# eightbyeight-ICN2012.net
KiCad netlist of a schematic drawn in EAGLE
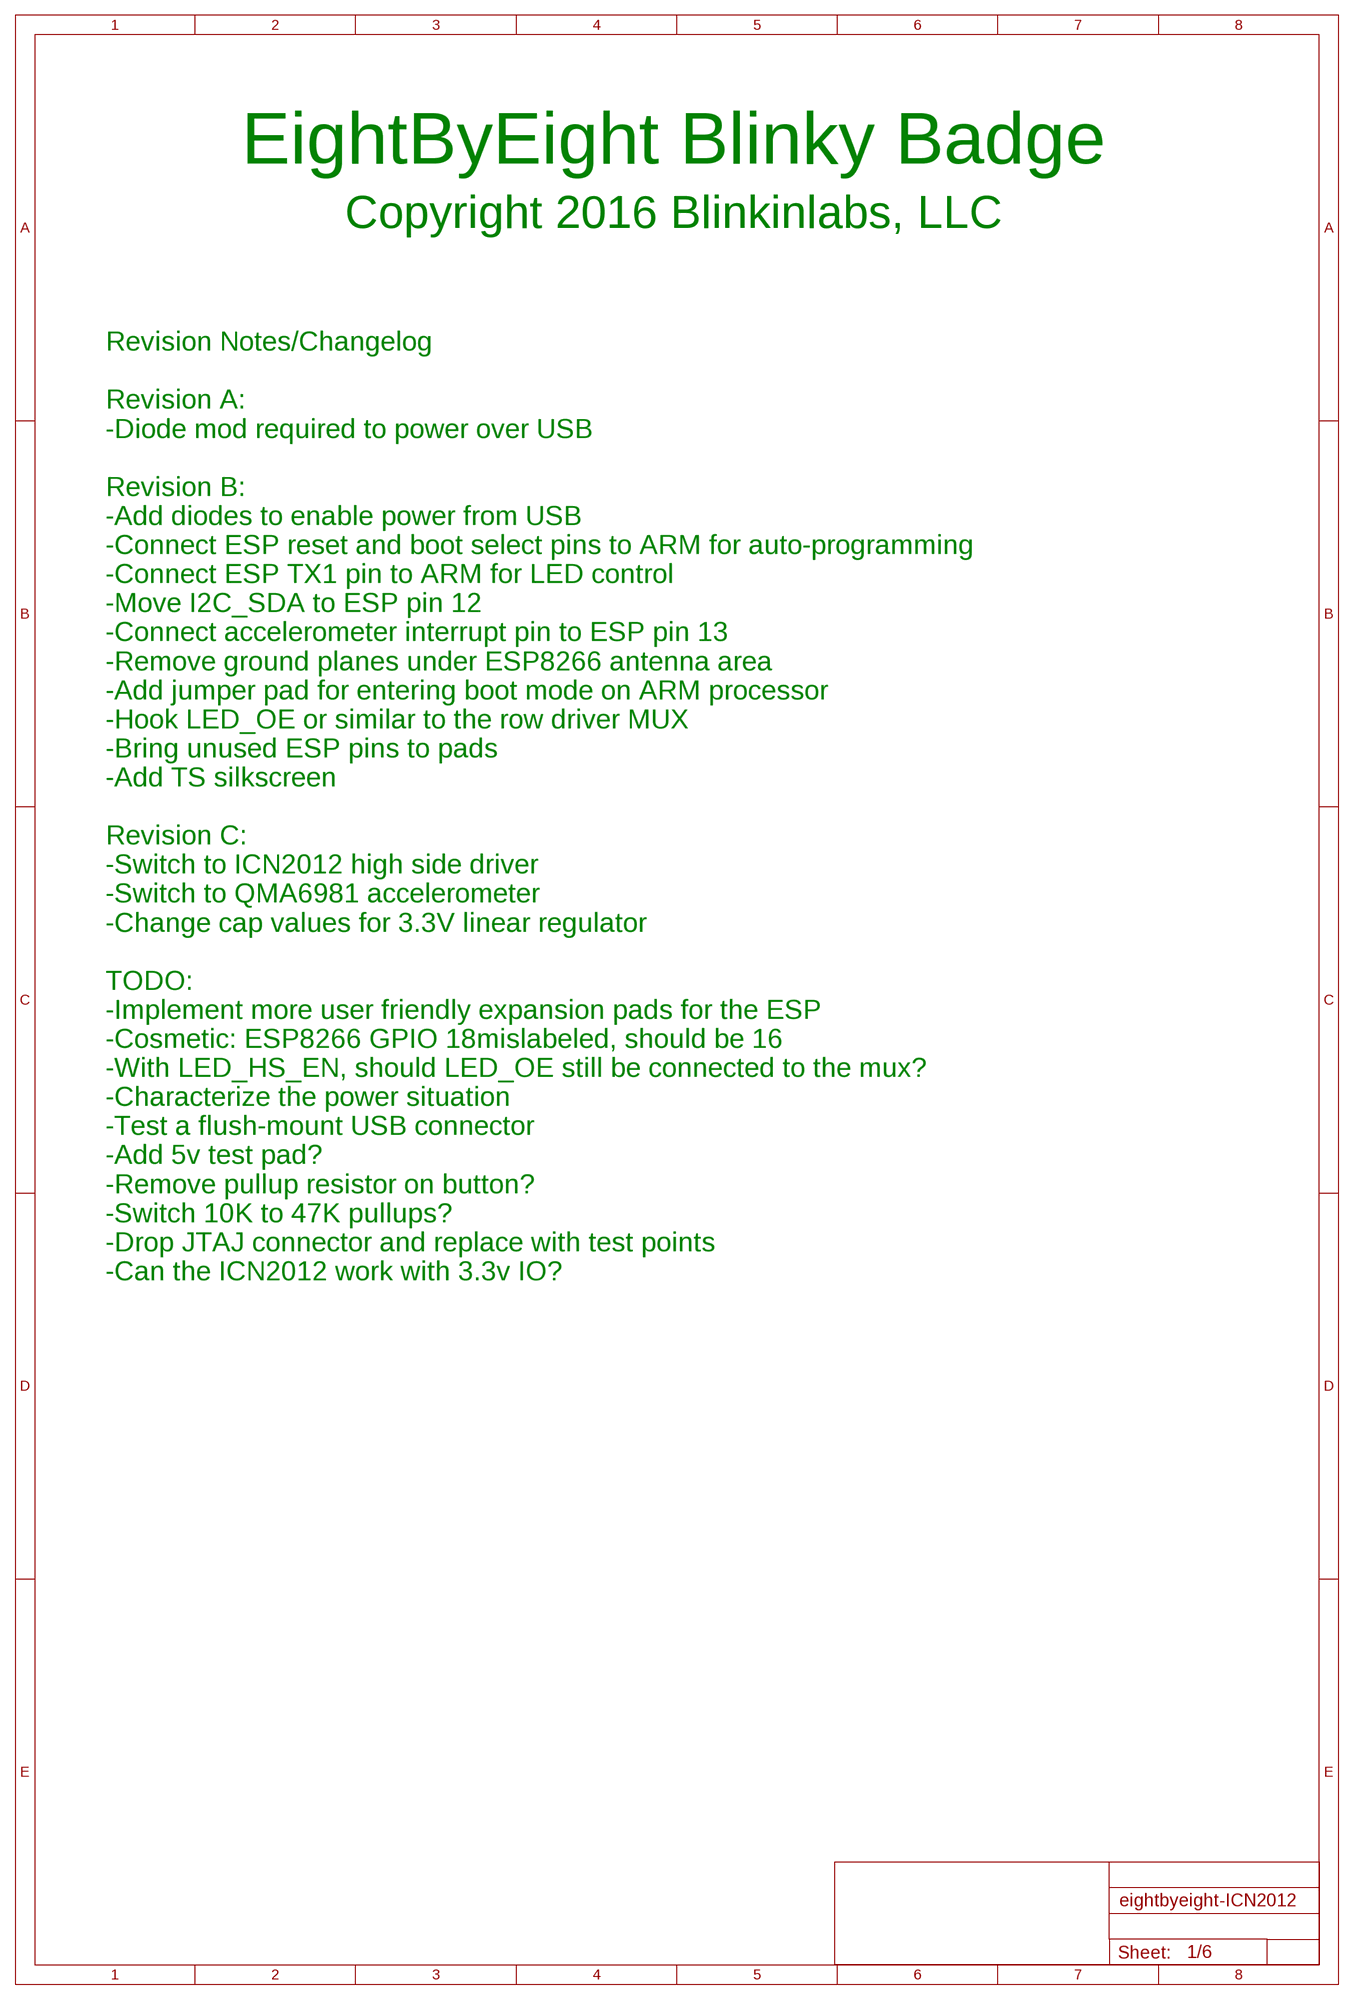
[diagram p0: schematic, sheet 1]
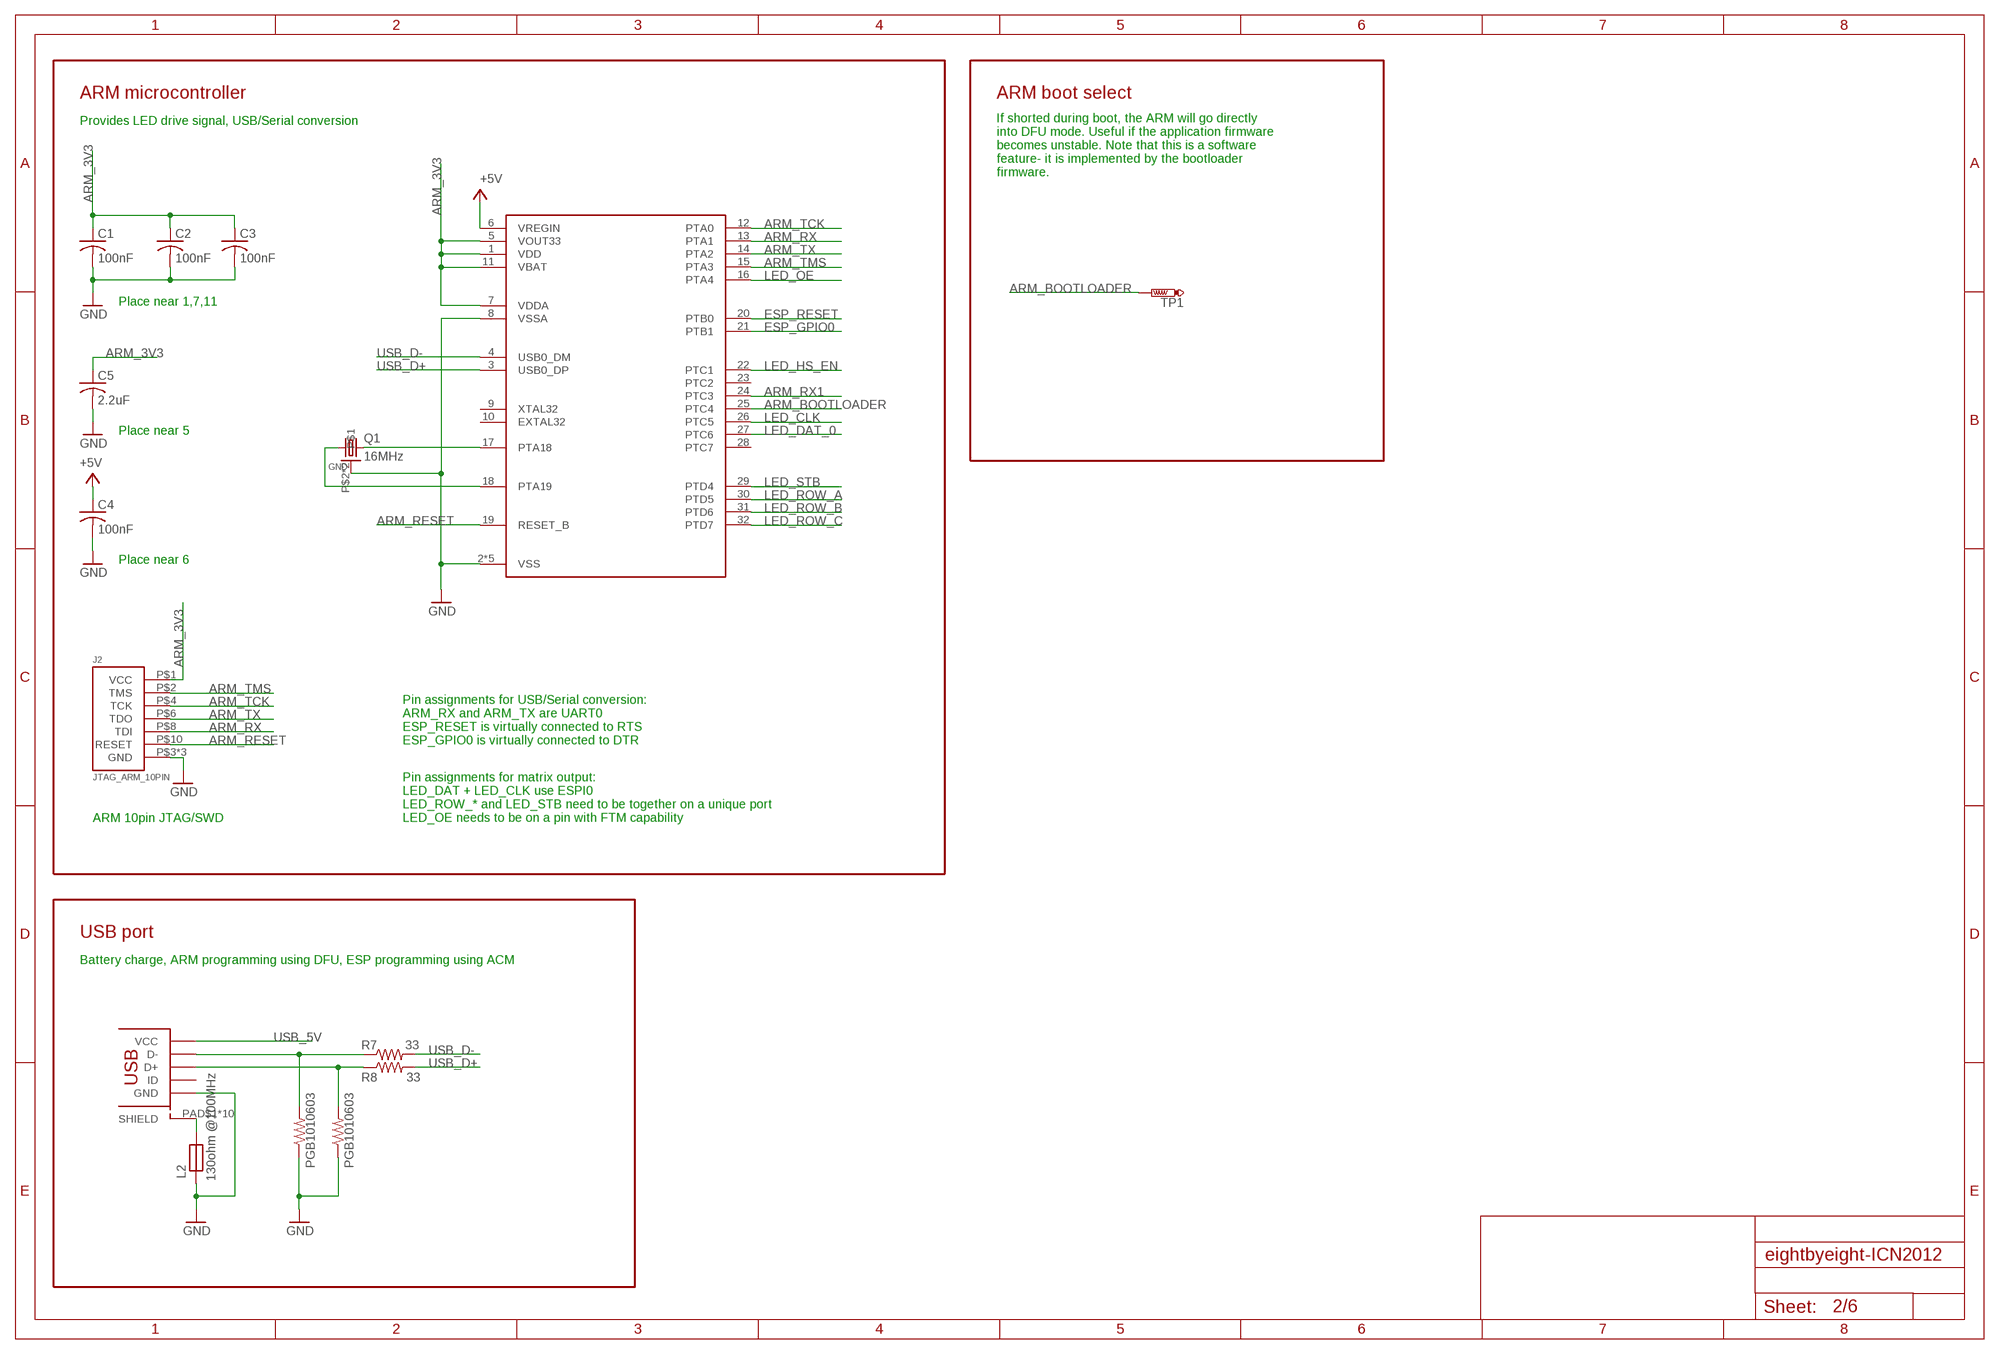
[diagram p1: schematic, sheet 2]
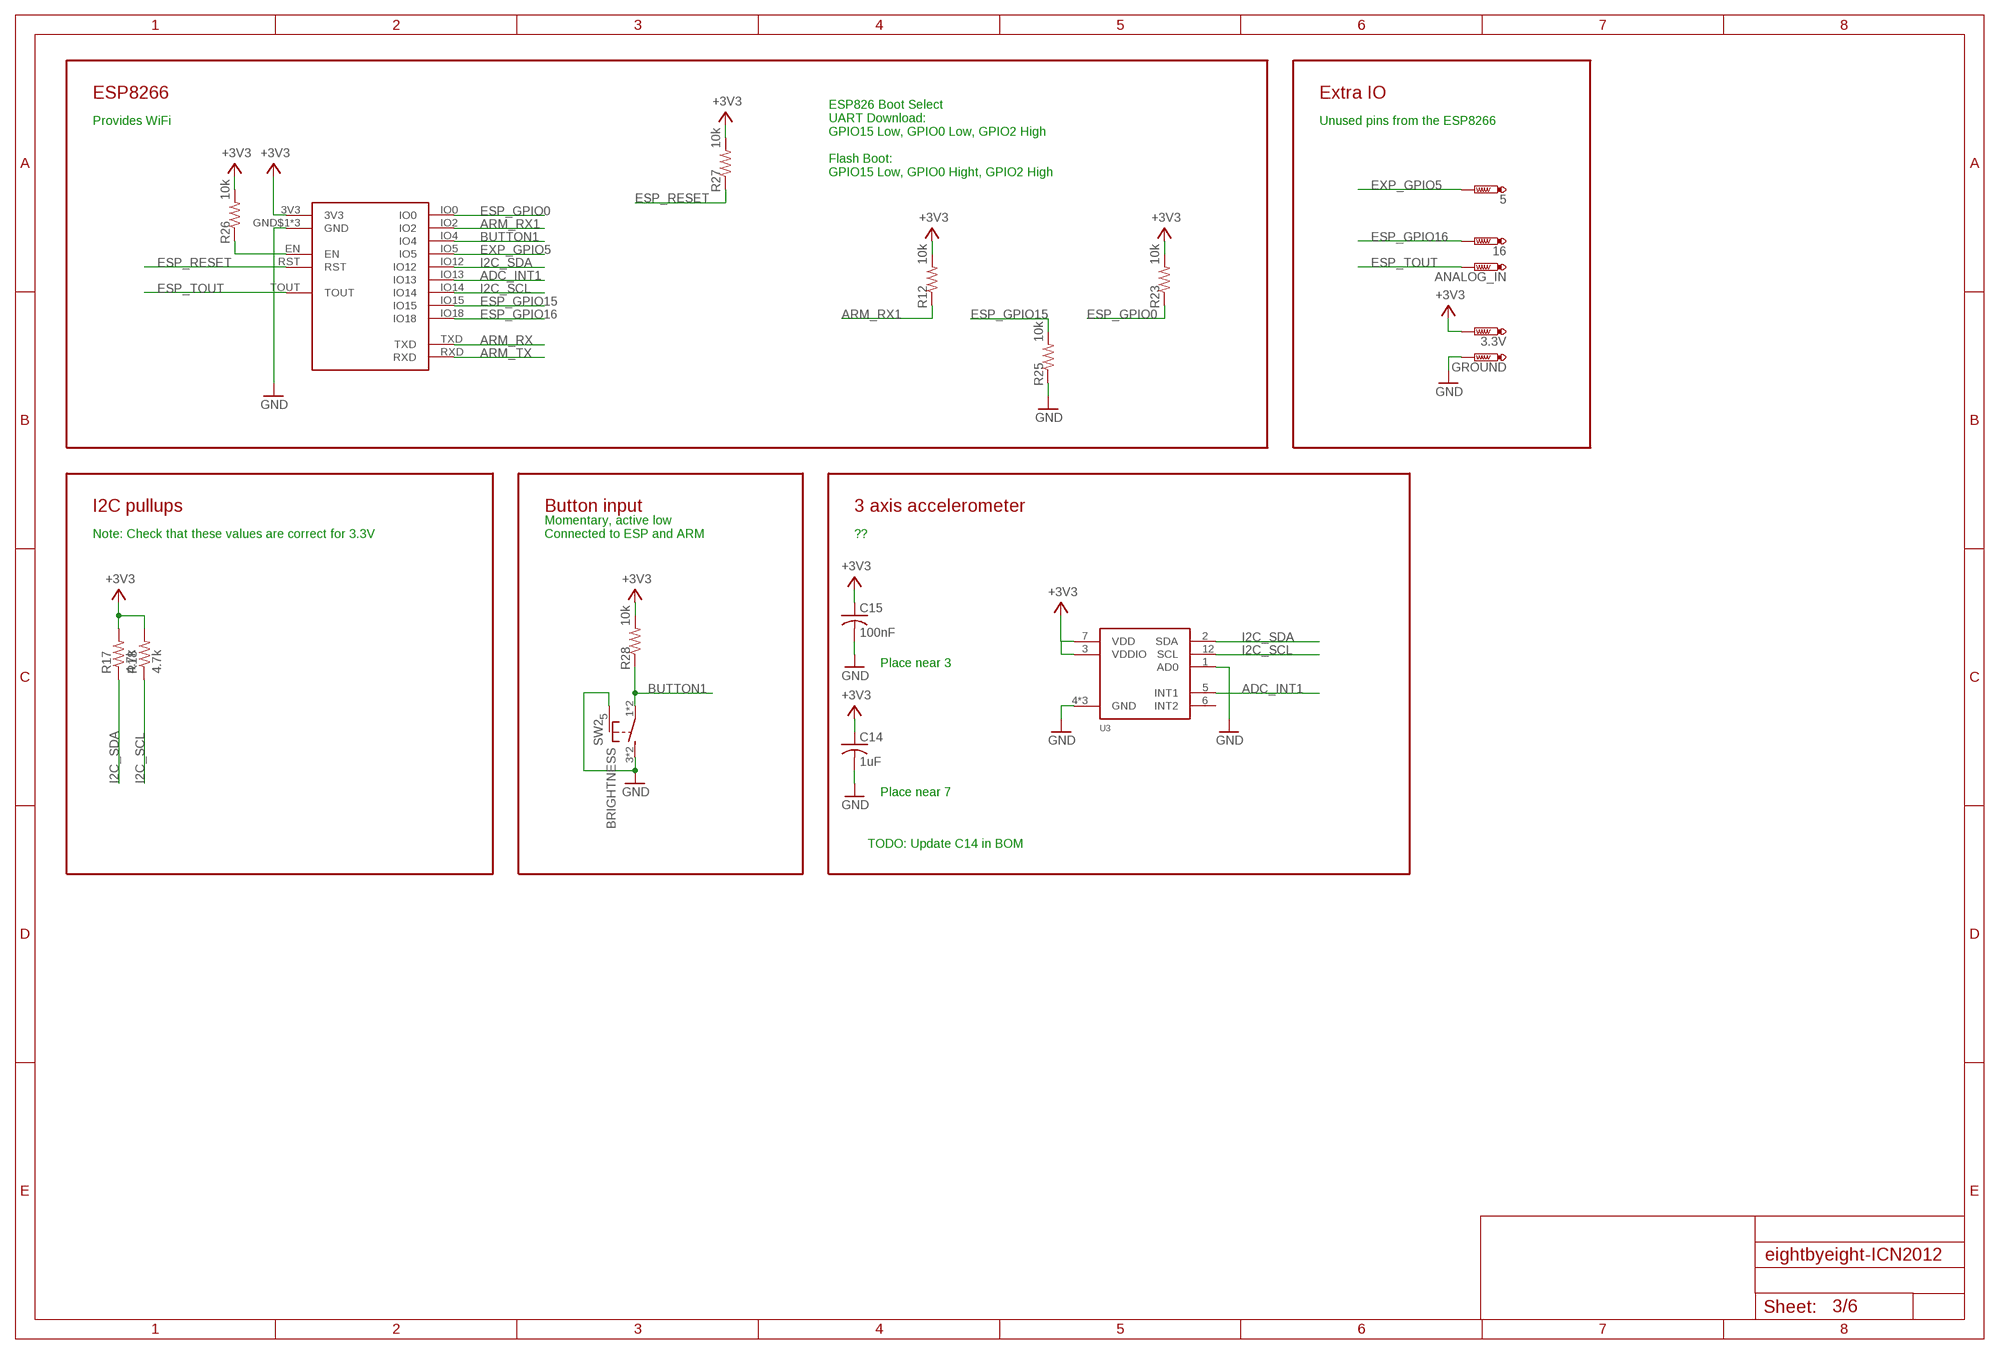
[diagram p2: schematic, sheet 3]
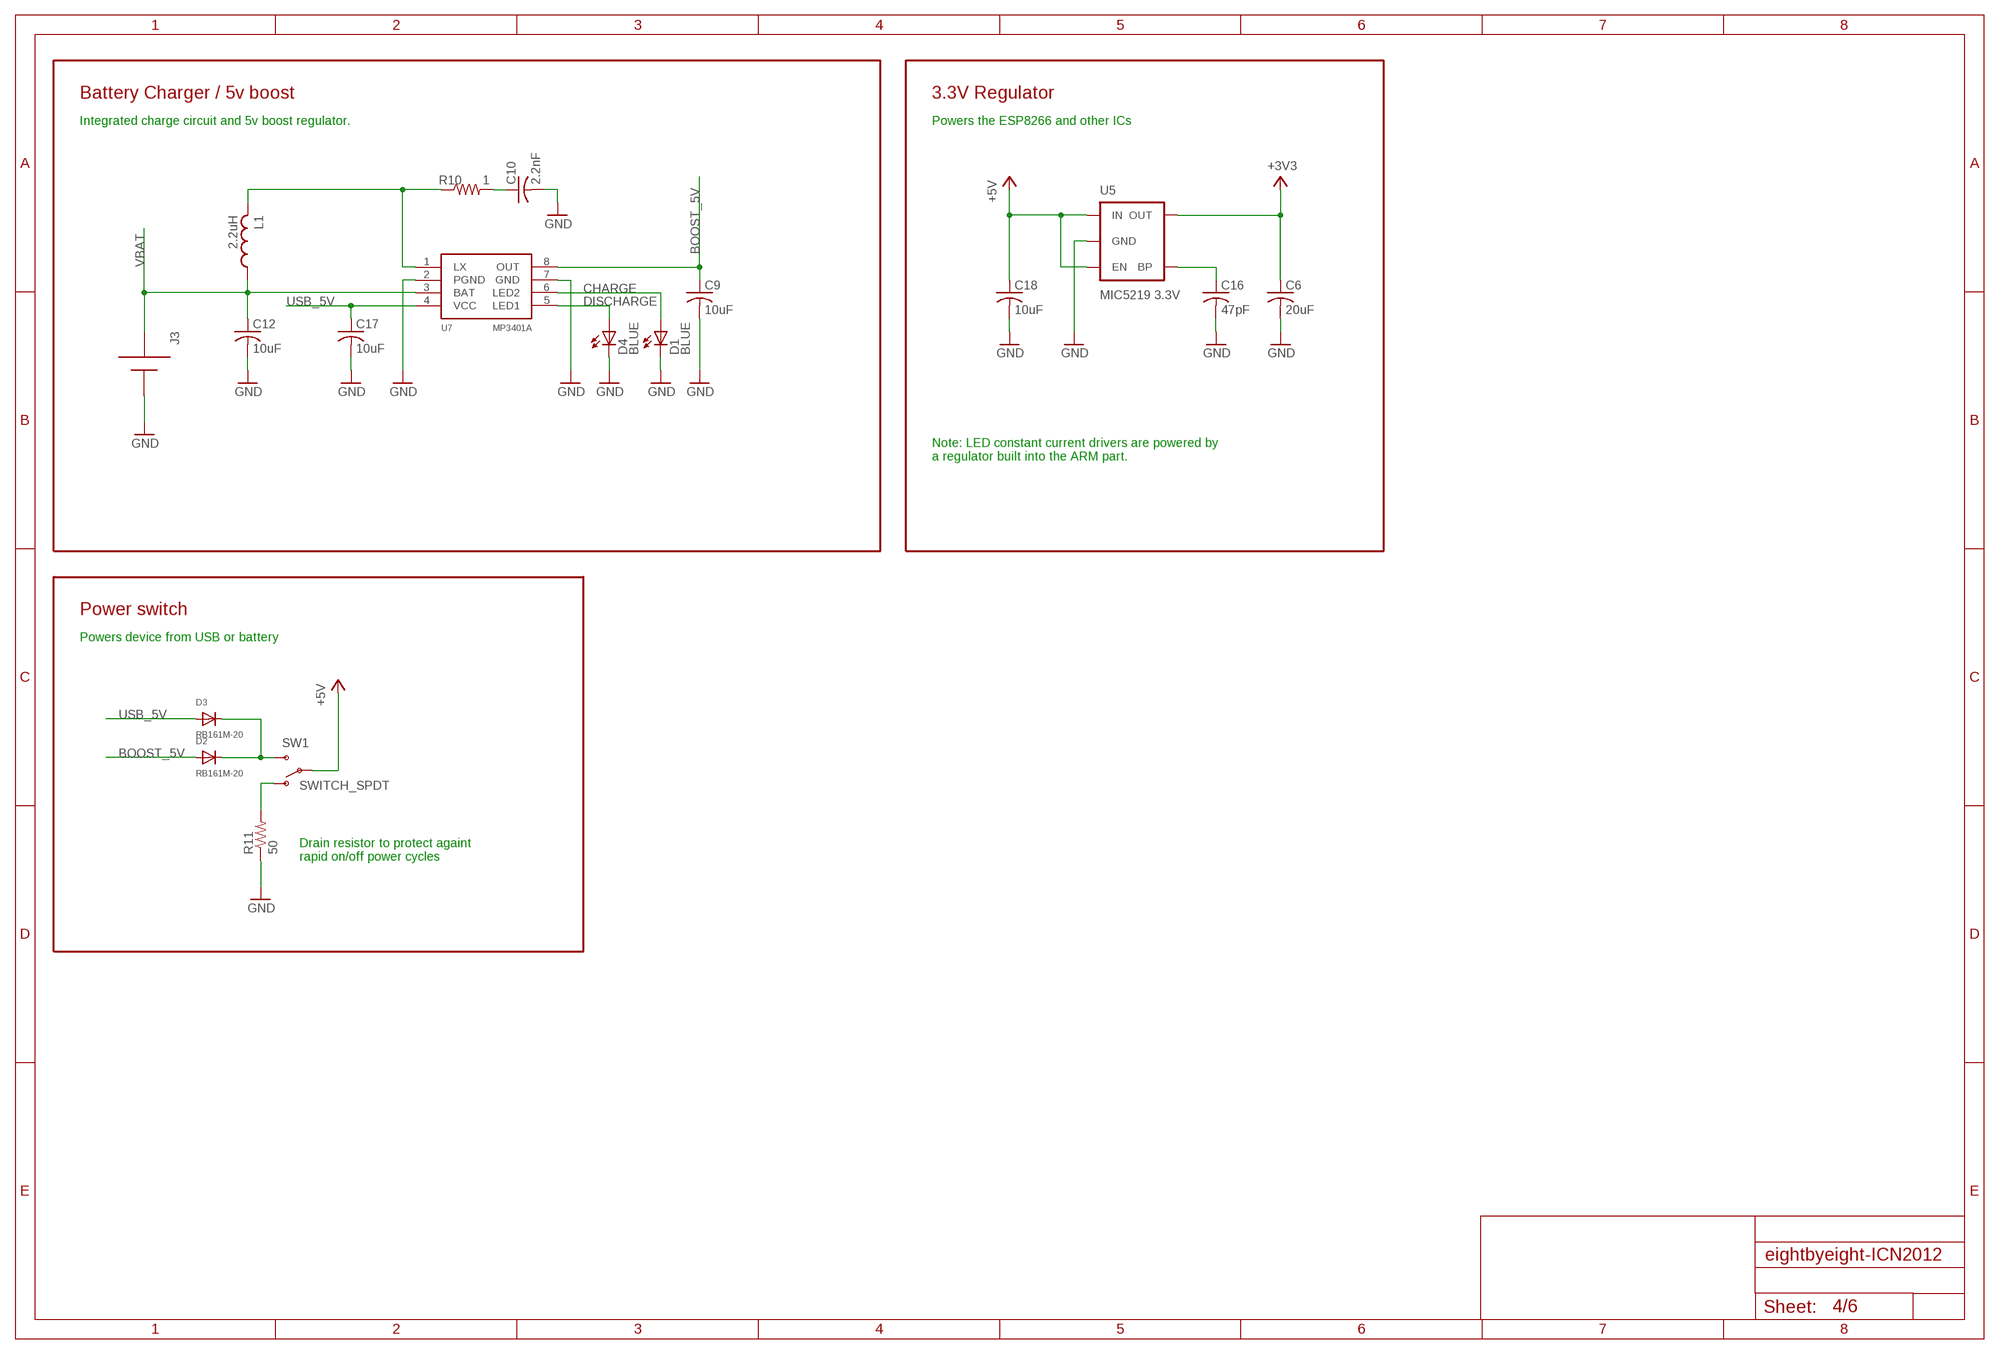
[diagram p3: schematic, sheet 4]
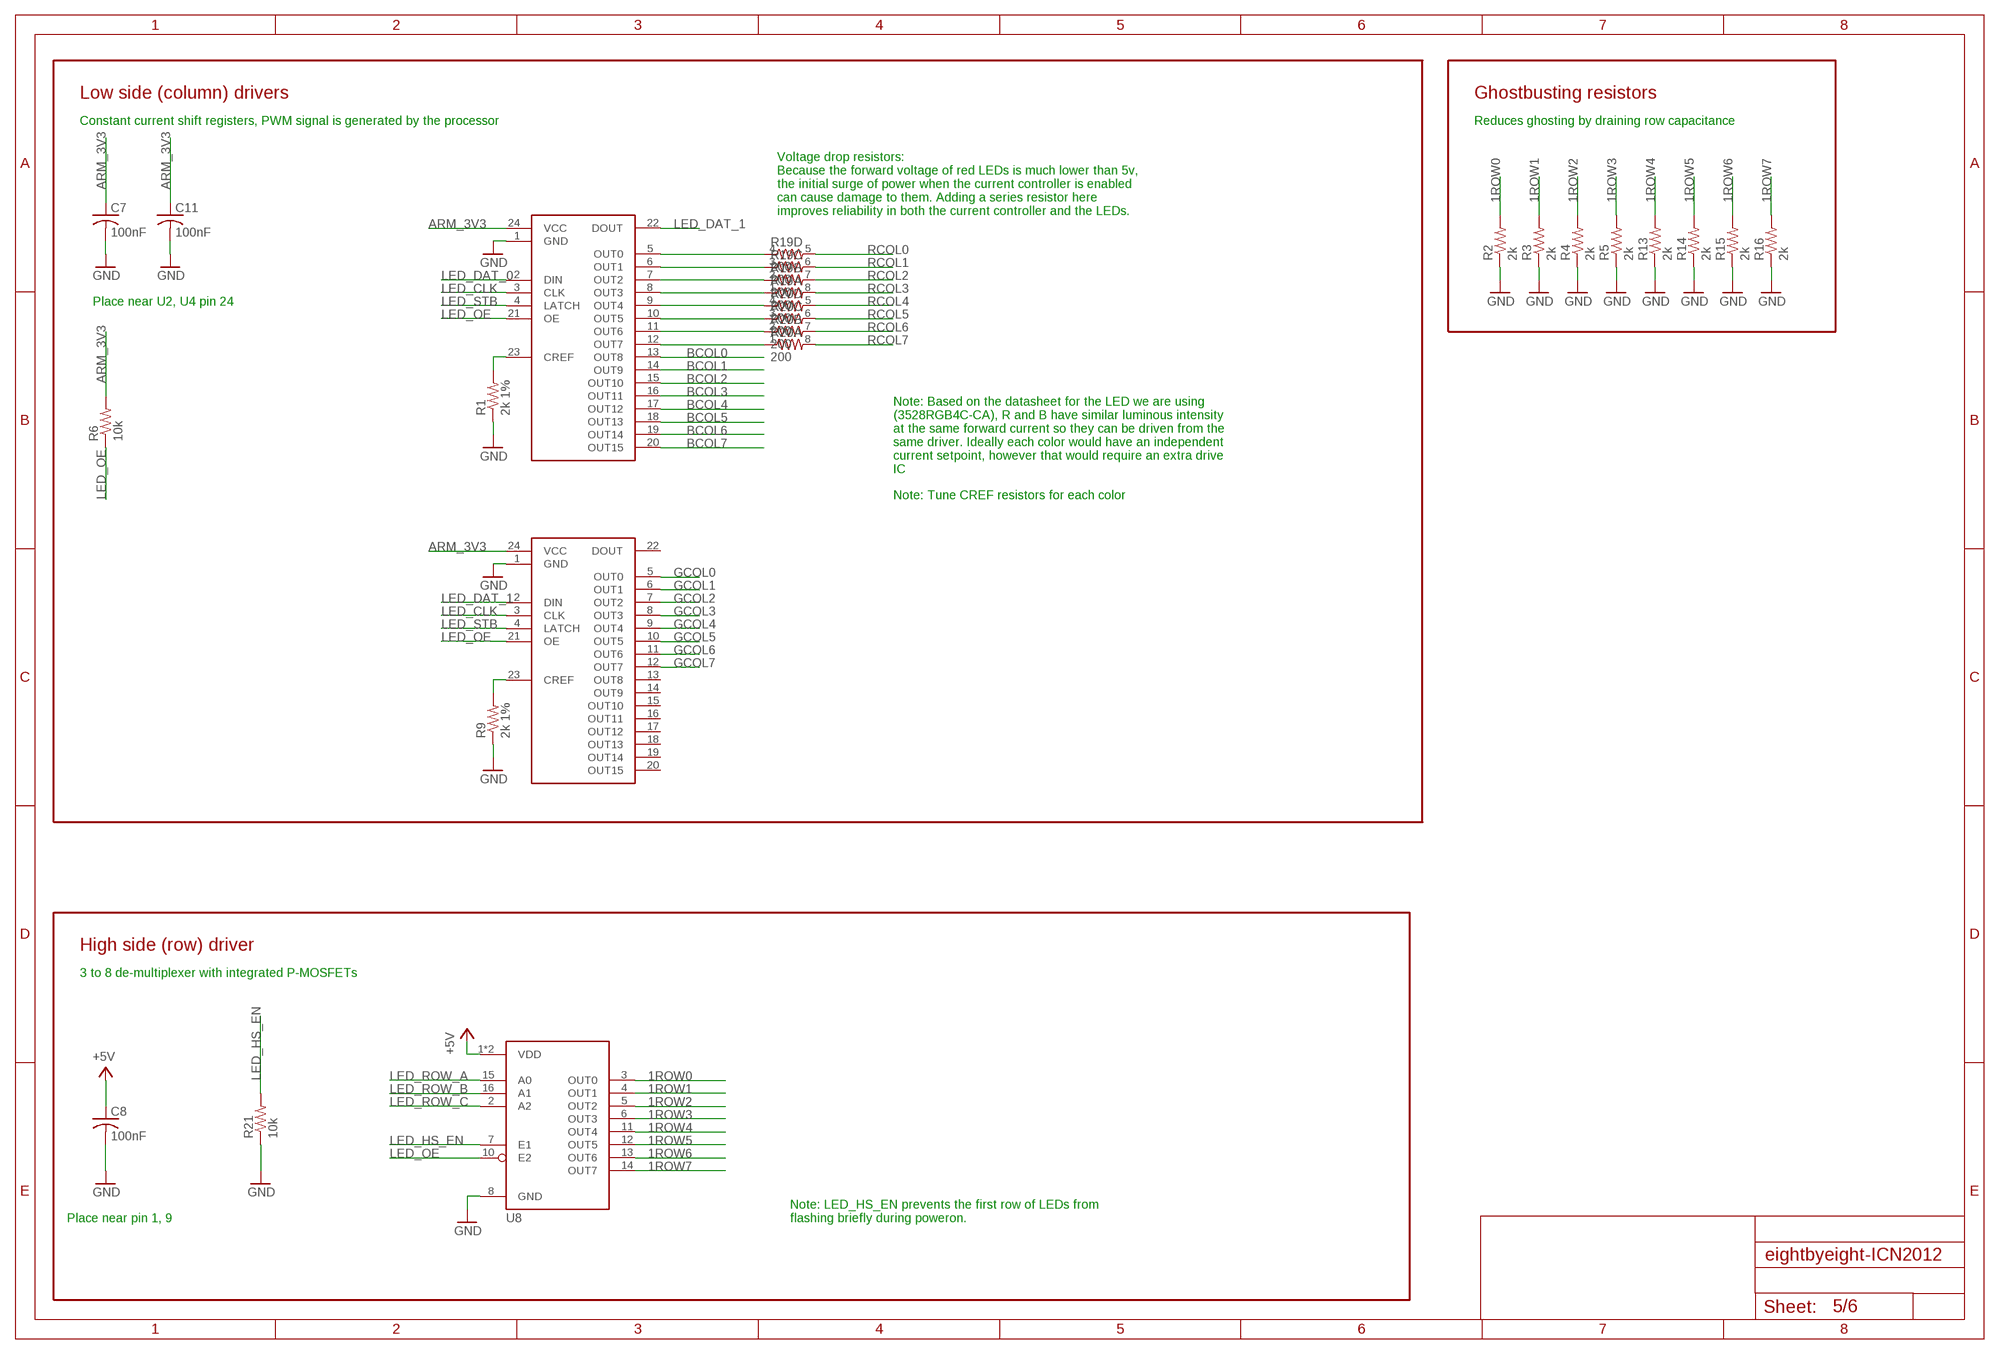
[diagram p4: schematic, sheet 5]
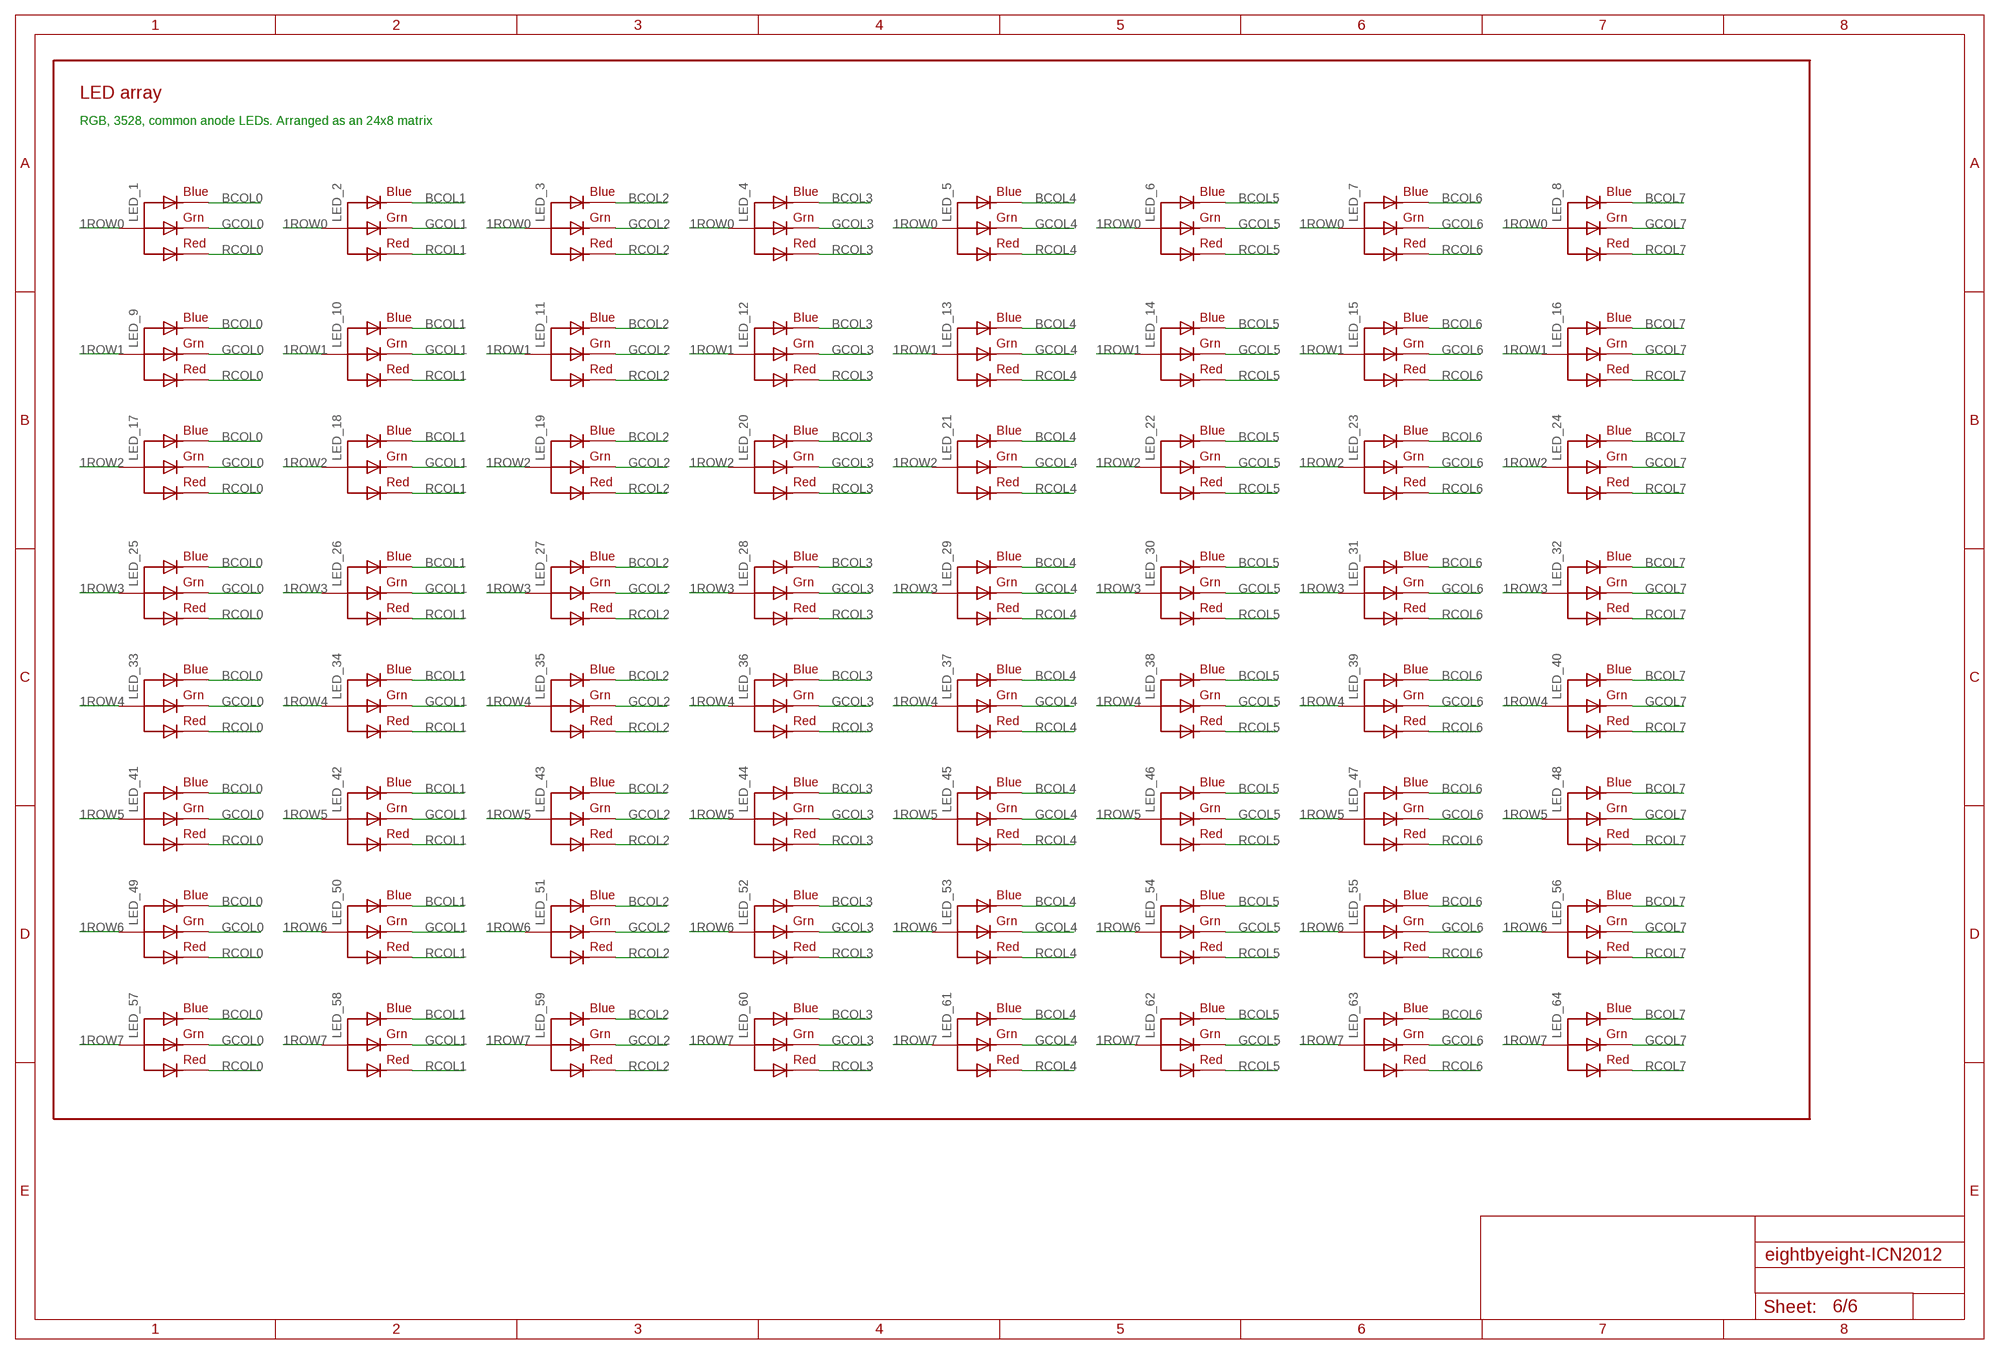
[diagram p5: schematic, sheet 6]

(export (version "E")
  (design (tool "Eeschema 10.0.6"))
  (components
    (comp (ref "LED_1")
      (value "LED_RGB_CA")
      (footprint "eagle-import:LED_3528")
      (libsource (lib "eagle-import") (part "LED_RGB_CA"))
    )
    (comp (ref "LED_2")
      (value "LED_RGB_CA")
      (footprint "eagle-import:LED_3528")
      (libsource (lib "eagle-import") (part "LED_RGB_CA"))
    )
    (comp (ref "LED_3")
      (value "LED_RGB_CA")
      (footprint "eagle-import:LED_3528")
      (libsource (lib "eagle-import") (part "LED_RGB_CA"))
    )
    (comp (ref "LED_4")
      (value "LED_RGB_CA")
      (footprint "eagle-import:LED_3528")
      (libsource (lib "eagle-import") (part "LED_RGB_CA"))
    )
    (comp (ref "LED_5")
      (value "LED_RGB_CA")
      (footprint "eagle-import:LED_3528")
      (libsource (lib "eagle-import") (part "LED_RGB_CA"))
    )
    (comp (ref "LED_6")
      (value "LED_RGB_CA")
      (footprint "eagle-import:LED_3528")
      (libsource (lib "eagle-import") (part "LED_RGB_CA"))
    )
    (comp (ref "LED_7")
      (value "LED_RGB_CA")
      (footprint "eagle-import:LED_3528")
      (libsource (lib "eagle-import") (part "LED_RGB_CA"))
    )
    (comp (ref "LED_8")
      (value "LED_RGB_CA")
      (footprint "eagle-import:LED_3528")
      (libsource (lib "eagle-import") (part "LED_RGB_CA"))
    )
    (comp (ref "LED_9")
      (value "LED_RGB_CA")
      (footprint "eagle-import:LED_3528")
      (libsource (lib "eagle-import") (part "LED_RGB_CA"))
    )
    (comp (ref "LED_10")
      (value "LED_RGB_CA")
      (footprint "eagle-import:LED_3528")
      (libsource (lib "eagle-import") (part "LED_RGB_CA"))
    )
    (comp (ref "LED_11")
      (value "LED_RGB_CA")
      (footprint "eagle-import:LED_3528")
      (libsource (lib "eagle-import") (part "LED_RGB_CA"))
    )
    (comp (ref "LED_12")
      (value "LED_RGB_CA")
      (footprint "eagle-import:LED_3528")
      (libsource (lib "eagle-import") (part "LED_RGB_CA"))
    )
    (comp (ref "LED_13")
      (value "LED_RGB_CA")
      (footprint "eagle-import:LED_3528")
      (libsource (lib "eagle-import") (part "LED_RGB_CA"))
    )
    (comp (ref "LED_14")
      (value "LED_RGB_CA")
      (footprint "eagle-import:LED_3528")
      (libsource (lib "eagle-import") (part "LED_RGB_CA"))
    )
    (comp (ref "LED_15")
      (value "LED_RGB_CA")
      (footprint "eagle-import:LED_3528")
      (libsource (lib "eagle-import") (part "LED_RGB_CA"))
    )
    (comp (ref "LED_16")
      (value "LED_RGB_CA")
      (footprint "eagle-import:LED_3528")
      (libsource (lib "eagle-import") (part "LED_RGB_CA"))
    )
    (comp (ref "LED_17")
      (value "LED_RGB_CA")
      (footprint "eagle-import:LED_3528")
      (libsource (lib "eagle-import") (part "LED_RGB_CA"))
    )
    (comp (ref "LED_18")
      (value "LED_RGB_CA")
      (footprint "eagle-import:LED_3528")
      (libsource (lib "eagle-import") (part "LED_RGB_CA"))
    )
    (comp (ref "LED_19")
      (value "LED_RGB_CA")
      (footprint "eagle-import:LED_3528")
      (libsource (lib "eagle-import") (part "LED_RGB_CA"))
    )
    (comp (ref "LED_20")
      (value "LED_RGB_CA")
      (footprint "eagle-import:LED_3528")
      (libsource (lib "eagle-import") (part "LED_RGB_CA"))
    )
    (comp (ref "LED_21")
      (value "LED_RGB_CA")
      (footprint "eagle-import:LED_3528")
      (libsource (lib "eagle-import") (part "LED_RGB_CA"))
    )
    (comp (ref "LED_22")
      (value "LED_RGB_CA")
      (footprint "eagle-import:LED_3528")
      (libsource (lib "eagle-import") (part "LED_RGB_CA"))
    )
    (comp (ref "LED_23")
      (value "LED_RGB_CA")
      (footprint "eagle-import:LED_3528")
      (libsource (lib "eagle-import") (part "LED_RGB_CA"))
    )
    (comp (ref "LED_24")
      (value "LED_RGB_CA")
      (footprint "eagle-import:LED_3528")
      (libsource (lib "eagle-import") (part "LED_RGB_CA"))
    )
    (comp (ref "LED_25")
      (value "LED_RGB_CA")
      (footprint "eagle-import:LED_3528")
      (libsource (lib "eagle-import") (part "LED_RGB_CA"))
    )
    (comp (ref "LED_26")
      (value "LED_RGB_CA")
      (footprint "eagle-import:LED_3528")
      (libsource (lib "eagle-import") (part "LED_RGB_CA"))
    )
    (comp (ref "LED_27")
      (value "LED_RGB_CA")
      (footprint "eagle-import:LED_3528")
      (libsource (lib "eagle-import") (part "LED_RGB_CA"))
    )
    (comp (ref "LED_28")
      (value "LED_RGB_CA")
      (footprint "eagle-import:LED_3528")
      (libsource (lib "eagle-import") (part "LED_RGB_CA"))
    )
    (comp (ref "LED_29")
      (value "LED_RGB_CA")
      (footprint "eagle-import:LED_3528")
      (libsource (lib "eagle-import") (part "LED_RGB_CA"))
    )
    (comp (ref "LED_30")
      (value "LED_RGB_CA")
      (footprint "eagle-import:LED_3528")
      (libsource (lib "eagle-import") (part "LED_RGB_CA"))
    )
    (comp (ref "LED_31")
      (value "LED_RGB_CA")
      (footprint "eagle-import:LED_3528")
      (libsource (lib "eagle-import") (part "LED_RGB_CA"))
    )
    (comp (ref "LED_32")
      (value "LED_RGB_CA")
      (footprint "eagle-import:LED_3528")
      (libsource (lib "eagle-import") (part "LED_RGB_CA"))
    )
    (comp (ref "LED_33")
      (value "LED_RGB_CA")
      (footprint "eagle-import:LED_3528")
      (libsource (lib "eagle-import") (part "LED_RGB_CA"))
    )
    (comp (ref "LED_34")
      (value "LED_RGB_CA")
      (footprint "eagle-import:LED_3528")
      (libsource (lib "eagle-import") (part "LED_RGB_CA"))
    )
    (comp (ref "LED_35")
      (value "LED_RGB_CA")
      (footprint "eagle-import:LED_3528")
      (libsource (lib "eagle-import") (part "LED_RGB_CA"))
    )
    (comp (ref "LED_36")
      (value "LED_RGB_CA")
      (footprint "eagle-import:LED_3528")
      (libsource (lib "eagle-import") (part "LED_RGB_CA"))
    )
    (comp (ref "LED_37")
      (value "LED_RGB_CA")
      (footprint "eagle-import:LED_3528")
      (libsource (lib "eagle-import") (part "LED_RGB_CA"))
    )
    (comp (ref "LED_38")
      (value "LED_RGB_CA")
      (footprint "eagle-import:LED_3528")
      (libsource (lib "eagle-import") (part "LED_RGB_CA"))
    )
    (comp (ref "LED_39")
      (value "LED_RGB_CA")
      (footprint "eagle-import:LED_3528")
      (libsource (lib "eagle-import") (part "LED_RGB_CA"))
    )
    (comp (ref "LED_40")
      (value "LED_RGB_CA")
      (footprint "eagle-import:LED_3528")
      (libsource (lib "eagle-import") (part "LED_RGB_CA"))
    )
    (comp (ref "LED_41")
      (value "LED_RGB_CA")
      (footprint "eagle-import:LED_3528")
      (libsource (lib "eagle-import") (part "LED_RGB_CA"))
    )
    (comp (ref "LED_42")
      (value "LED_RGB_CA")
      (footprint "eagle-import:LED_3528")
      (libsource (lib "eagle-import") (part "LED_RGB_CA"))
    )
    (comp (ref "LED_43")
      (value "LED_RGB_CA")
      (footprint "eagle-import:LED_3528")
      (libsource (lib "eagle-import") (part "LED_RGB_CA"))
    )
    (comp (ref "LED_44")
      (value "LED_RGB_CA")
      (footprint "eagle-import:LED_3528")
      (libsource (lib "eagle-import") (part "LED_RGB_CA"))
    )
    (comp (ref "LED_45")
      (value "LED_RGB_CA")
      (footprint "eagle-import:LED_3528")
      (libsource (lib "eagle-import") (part "LED_RGB_CA"))
    )
    (comp (ref "LED_46")
      (value "LED_RGB_CA")
      (footprint "eagle-import:LED_3528")
      (libsource (lib "eagle-import") (part "LED_RGB_CA"))
    )
    (comp (ref "LED_47")
      (value "LED_RGB_CA")
      (footprint "eagle-import:LED_3528")
      (libsource (lib "eagle-import") (part "LED_RGB_CA"))
    )
    (comp (ref "LED_48")
      (value "LED_RGB_CA")
      (footprint "eagle-import:LED_3528")
      (libsource (lib "eagle-import") (part "LED_RGB_CA"))
    )
    (comp (ref "LED_49")
      (value "LED_RGB_CA")
      (footprint "eagle-import:LED_3528")
      (libsource (lib "eagle-import") (part "LED_RGB_CA"))
    )
    (comp (ref "LED_50")
      (value "LED_RGB_CA")
      (footprint "eagle-import:LED_3528")
      (libsource (lib "eagle-import") (part "LED_RGB_CA"))
    )
    (comp (ref "LED_51")
      (value "LED_RGB_CA")
      (footprint "eagle-import:LED_3528")
      (libsource (lib "eagle-import") (part "LED_RGB_CA"))
    )
    (comp (ref "LED_52")
      (value "LED_RGB_CA")
      (footprint "eagle-import:LED_3528")
      (libsource (lib "eagle-import") (part "LED_RGB_CA"))
    )
    (comp (ref "LED_53")
      (value "LED_RGB_CA")
      (footprint "eagle-import:LED_3528")
      (libsource (lib "eagle-import") (part "LED_RGB_CA"))
    )
    (comp (ref "LED_54")
      (value "LED_RGB_CA")
      (footprint "eagle-import:LED_3528")
      (libsource (lib "eagle-import") (part "LED_RGB_CA"))
    )
    (comp (ref "LED_55")
      (value "LED_RGB_CA")
      (footprint "eagle-import:LED_3528")
      (libsource (lib "eagle-import") (part "LED_RGB_CA"))
    )
    (comp (ref "LED_56")
      (value "LED_RGB_CA")
      (footprint "eagle-import:LED_3528")
      (libsource (lib "eagle-import") (part "LED_RGB_CA"))
    )
    (comp (ref "LED_57")
      (value "LED_RGB_CA")
      (footprint "eagle-import:LED_3528")
      (libsource (lib "eagle-import") (part "LED_RGB_CA"))
    )
    (comp (ref "LED_58")
      (value "LED_RGB_CA")
      (footprint "eagle-import:LED_3528")
      (libsource (lib "eagle-import") (part "LED_RGB_CA"))
    )
    (comp (ref "LED_59")
      (value "LED_RGB_CA")
      (footprint "eagle-import:LED_3528")
      (libsource (lib "eagle-import") (part "LED_RGB_CA"))
    )
    (comp (ref "LED_60")
      (value "LED_RGB_CA")
      (footprint "eagle-import:LED_3528")
      (libsource (lib "eagle-import") (part "LED_RGB_CA"))
    )
    (comp (ref "LED_61")
      (value "LED_RGB_CA")
      (footprint "eagle-import:LED_3528")
      (libsource (lib "eagle-import") (part "LED_RGB_CA"))
    )
    (comp (ref "LED_62")
      (value "LED_RGB_CA")
      (footprint "eagle-import:LED_3528")
      (libsource (lib "eagle-import") (part "LED_RGB_CA"))
    )
    (comp (ref "LED_63")
      (value "LED_RGB_CA")
      (footprint "eagle-import:LED_3528")
      (libsource (lib "eagle-import") (part "LED_RGB_CA"))
    )
    (comp (ref "LED_64")
      (value "LED_RGB_CA")
      (footprint "eagle-import:LED_3528")
      (libsource (lib "eagle-import") (part "LED_RGB_CA"))
    )
    (comp (ref "C6")
      (value "20uF")
      (footprint "eagle-import:C0805")
      (libsource (lib "eagle-import") (part "C-USC0805"))
    )
    (comp (ref "C9")
      (value "10uF")
      (footprint "eagle-import:C0805")
      (libsource (lib "eagle-import") (part "C-USC0805"))
    )
    (comp (ref "C10")
      (value "2.2nF")
      (footprint "eagle-import:C0603")
      (libsource (lib "eagle-import") (part "C-USC0603"))
    )
    (comp (ref "C12")
      (value "10uF")
      (footprint "eagle-import:C0805")
      (libsource (lib "eagle-import") (part "C-USC0805"))
    )
    (comp (ref "C16")
      (value "47pF")
      (footprint "eagle-import:C0402")
      (libsource (lib "eagle-import") (part "C-USC0402"))
    )
    (comp (ref "C17")
      (value "10uF")
      (footprint "eagle-import:C0805")
      (libsource (lib "eagle-import") (part "C-USC0805"))
    )
    (comp (ref "C18")
      (value "10uF")
      (footprint "eagle-import:C0805")
      (libsource (lib "eagle-import") (part "C-USC0805"))
    )
    (comp (ref "D1")
      (value "BLUE")
      (footprint "eagle-import:CHIP-LED0603")
      (libsource (lib "eagle-import") (part "LEDCHIP-LED0603"))
    )
    (comp (ref "D2")
      (value "RB161M-20")
      (footprint "eagle-import:SOD-123")
      (libsource (lib "eagle-import") (part "DIODESOD-123"))
    )
    (comp (ref "D3")
      (value "RB161M-20")
      (footprint "eagle-import:SOD-123")
      (libsource (lib "eagle-import") (part "DIODESOD-123"))
    )
    (comp (ref "D4")
      (value "BLUE")
      (footprint "eagle-import:CHIP-LED0603")
      (libsource (lib "eagle-import") (part "LEDCHIP-LED0603"))
    )
    (comp (ref "J3")
      (value "BATTERY")
      (footprint "eagle-import:BATTERY_AA_SMD")
      (libsource (lib "eagle-import") (part "BATTERY"))
    )
    (comp (ref "L1")
      (value "2.2uH")
      (footprint "eagle-import:INDUCTOR_CD43")
      (libsource (lib "eagle-import") (part "LCD43"))
    )
    (comp (ref "R10")
      (value "1")
      (footprint "eagle-import:R0603")
      (libsource (lib "eagle-import") (part "R-US_R0603"))
    )
    (comp (ref "R11")
      (value "50")
      (footprint "eagle-import:R0805")
      (libsource (lib "eagle-import") (part "R-US_R0805"))
    )
    (comp (ref "SW1")
      (value "SWITCH_SPDT")
      (footprint "eagle-import:SWITCH_6P-2POS")
      (libsource (lib "eagle-import") (part "SWITCH_SPDT"))
    )
    (comp (ref "U5")
      (value "MIC5219 3.3V")
      (footprint "eagle-import:SOT23-5")
      (libsource (lib "eagle-import") (part "V_REG_MIC52193.3V"))
    )
    (comp (ref "U7")
      (value "MP3401A")
      (footprint "eagle-import:SO08-150")
      (libsource (lib "eagle-import") (part "MP3401A"))
    )
    (comp (ref "C7")
      (value "100nF")
      (footprint "eagle-import:C0402")
      (libsource (lib "eagle-import") (part "C-USC0402"))
    )
    (comp (ref "C8")
      (value "100nF")
      (footprint "eagle-import:C0402")
      (libsource (lib "eagle-import") (part "C-USC0402"))
    )
    (comp (ref "C11")
      (value "100nF")
      (footprint "eagle-import:C0402")
      (libsource (lib "eagle-import") (part "C-USC0402"))
    )
    (comp (ref "R1")
      (value "2k 1%")
      (footprint "eagle-import:R0402")
      (libsource (lib "eagle-import") (part "R-US_R0402"))
    )
    (comp (ref "R2")
      (value "2k")
      (footprint "eagle-import:R0402")
      (libsource (lib "eagle-import") (part "R-US_R0402"))
    )
    (comp (ref "R3")
      (value "2k")
      (footprint "eagle-import:R0402")
      (libsource (lib "eagle-import") (part "R-US_R0402"))
    )
    (comp (ref "R4")
      (value "2k")
      (footprint "eagle-import:R0402")
      (libsource (lib "eagle-import") (part "R-US_R0402"))
    )
    (comp (ref "R5")
      (value "2k")
      (footprint "eagle-import:R0402")
      (libsource (lib "eagle-import") (part "R-US_R0402"))
    )
    (comp (ref "R6")
      (value "10k")
      (footprint "eagle-import:R0402")
      (libsource (lib "eagle-import") (part "R-US_R0402"))
    )
    (comp (ref "R9")
      (value "2k 1%")
      (footprint "eagle-import:R0402")
      (libsource (lib "eagle-import") (part "R-US_R0402"))
    )
    (comp (ref "R13")
      (value "2k")
      (footprint "eagle-import:R0402")
      (libsource (lib "eagle-import") (part "R-US_R0402"))
    )
    (comp (ref "R14")
      (value "2k")
      (footprint "eagle-import:R0402")
      (libsource (lib "eagle-import") (part "R-US_R0402"))
    )
    (comp (ref "R15")
      (value "2k")
      (footprint "eagle-import:R0402")
      (libsource (lib "eagle-import") (part "R-US_R0402"))
    )
    (comp (ref "R16")
      (value "2k")
      (footprint "eagle-import:R0402")
      (libsource (lib "eagle-import") (part "R-US_R0402"))
    )
    (comp (ref "R19")
      (value "200")
      (footprint "eagle-import:0603-ARV")
      (libsource (lib "eagle-import") (part "RESISTOR-ARRAY0603-ARV"))
    )
    (comp (ref "R20")
      (value "200")
      (footprint "eagle-import:0603-ARV")
      (libsource (lib "eagle-import") (part "RESISTOR-ARRAY0603-ARV"))
    )
    (comp (ref "R21")
      (value "10k")
      (footprint "eagle-import:R0402")
      (libsource (lib "eagle-import") (part "R-US_R0402"))
    )
    (comp (ref "U2")
      (value "ICN2027")
      (footprint "eagle-import:SSOP24-150")
      (libsource (lib "eagle-import") (part "ICN2026"))
    )
    (comp (ref "U4")
      (value "ICN2027")
      (footprint "eagle-import:SSOP24-150")
      (libsource (lib "eagle-import") (part "ICN2026"))
    )
    (comp (ref "U8")
      (value "ICN2012")
      (footprint "eagle-import:SO16")
      (libsource (lib "eagle-import") (part "ICN2012"))
    )
    (comp (ref "C1")
      (value "100nF")
      (footprint "eagle-import:C0402")
      (libsource (lib "eagle-import") (part "C-USC0402"))
    )
    (comp (ref "C2")
      (value "100nF")
      (footprint "eagle-import:C0402")
      (libsource (lib "eagle-import") (part "C-USC0402"))
    )
    (comp (ref "C3")
      (value "100nF")
      (footprint "eagle-import:C0402")
      (libsource (lib "eagle-import") (part "C-USC0402"))
    )
    (comp (ref "C4")
      (value "100nF")
      (footprint "eagle-import:C0402")
      (libsource (lib "eagle-import") (part "C-USC0402"))
    )
    (comp (ref "C5")
      (value "2.2uF")
      (footprint "eagle-import:C0402")
      (libsource (lib "eagle-import") (part "C-USC0402"))
    )
    (comp (ref "J1")
      (value "USB_MICROSMT+THRUHULE")
      (footprint "eagle-import:USB_MICRO_THRUHOLE")
      (libsource (lib "eagle-import") (part "USB_MICROSMT+THRUHULE"))
    )
    (comp (ref "J2")
      (value "JTAG_ARM_10PIN")
      (footprint "eagle-import:2X05-1.27MM-SMD")
      (libsource (lib "eagle-import") (part "JTAG_ARM_10PIN"))
    )
    (comp (ref "L2")
      (value "130ohm @100MHz")
      (footprint "eagle-import:0805")
      (libsource (lib "eagle-import") (part "FB0805/NO-OUTLINE"))
    )
    (comp (ref "Q1")
      (value "16MHz")
      (footprint "eagle-import:CRSYTAL_2520")
      (libsource (lib "eagle-import") (part "CRYSTAL_4PAD2520"))
    )
    (comp (ref "R7")
      (value "33")
      (footprint "eagle-import:R0402")
      (libsource (lib "eagle-import") (part "R-US_R0402"))
    )
    (comp (ref "R8")
      (value "33")
      (footprint "eagle-import:R0402")
      (libsource (lib "eagle-import") (part "R-US_R0402"))
    )
    (comp (ref "TP1")
      (value "PTR1B1,27")
      (footprint "eagle-import:B1,27")
      (libsource (lib "eagle-import") (part "PTR1B1,27"))
    )
    (comp (ref "U1")
      (value "MK20DN32VFM5")
      (footprint "eagle-import:QFN32_5X5_LONGLEADS")
      (libsource (lib "eagle-import") (part "MK20D--VFM5"))
    )
    (comp (ref "Z1")
      (value "PGB1010603")
      (footprint "eagle-import:SPARKFUN-RESISTORS_0603-RES")
      (fields (field (name "MF") "Littelfuse") (field (name "MPN") "PGB1010603NRHF"))
      (libsource (lib "eagle-import") (part "SPARKFUN-RESISTORS_RESISTOR0603-RES"))
    )
    (comp (ref "Z2")
      (value "PGB1010603")
      (footprint "eagle-import:SPARKFUN-RESISTORS_0603-RES")
      (fields (field (name "MF") "Littelfuse") (field (name "MPN") "PGB1010603NRHF"))
      (libsource (lib "eagle-import") (part "SPARKFUN-RESISTORS_RESISTOR0603-RES"))
    )
    (comp (ref "3.3V")
      (value "PTR1B2,54")
      (footprint "eagle-import:B2,54")
      (libsource (lib "eagle-import") (part "PTR1B2,54"))
    )
    (comp (ref "5")
      (value "PTR1B2,54")
      (footprint "eagle-import:B2,54")
      (libsource (lib "eagle-import") (part "PTR1B2,54"))
    )
    (comp (ref "16")
      (value "PTR1B2,54")
      (footprint "eagle-import:B2,54")
      (libsource (lib "eagle-import") (part "PTR1B2,54"))
    )
    (comp (ref "ANALOG_IN")
      (value "PTR1B2,54")
      (footprint "eagle-import:B2,54")
      (libsource (lib "eagle-import") (part "PTR1B2,54"))
    )
    (comp (ref "C14")
      (value "1uF")
      (footprint "eagle-import:C0402")
      (libsource (lib "eagle-import") (part "C-USC0402"))
    )
    (comp (ref "C15")
      (value "100nF")
      (footprint "eagle-import:C0402")
      (libsource (lib "eagle-import") (part "C-USC0402"))
    )
    (comp (ref "GROUND")
      (value "PTR1B2,54")
      (footprint "eagle-import:B2,54")
      (libsource (lib "eagle-import") (part "PTR1B2,54"))
    )
    (comp (ref "R12")
      (value "10k")
      (footprint "eagle-import:R0402")
      (libsource (lib "eagle-import") (part "R-US_R0402"))
    )
    (comp (ref "R17")
      (value "4.7k")
      (footprint "eagle-import:R0402")
      (libsource (lib "eagle-import") (part "R-US_R0402"))
    )
    (comp (ref "R18")
      (value "4.7k")
      (footprint "eagle-import:R0402")
      (libsource (lib "eagle-import") (part "R-US_R0402"))
    )
    (comp (ref "R23")
      (value "10k")
      (footprint "eagle-import:R0402")
      (libsource (lib "eagle-import") (part "R-US_R0402"))
    )
    (comp (ref "R25")
      (value "10k")
      (footprint "eagle-import:R0402")
      (libsource (lib "eagle-import") (part "R-US_R0402"))
    )
    (comp (ref "R26")
      (value "10k")
      (footprint "eagle-import:R0402")
      (libsource (lib "eagle-import") (part "R-US_R0402"))
    )
    (comp (ref "R27")
      (value "10k")
      (footprint "eagle-import:R0402")
      (libsource (lib "eagle-import") (part "R-US_R0402"))
    )
    (comp (ref "R28")
      (value "10k")
      (footprint "eagle-import:R0402")
      (libsource (lib "eagle-import") (part "R-US_R0402"))
    )
    (comp (ref "SW2")
      (value "BRIGHTNESS")
      (footprint "eagle-import:TD-07XB")
      (libsource (lib "eagle-import") (part "BUTTON_MOMENTARY_GROUND"))
    )
    (comp (ref "U3")
      (value "QMA6981")
      (footprint "eagle-import:LGA2X2MM")
      (libsource (lib "eagle-import") (part "QMA6981"))
    )
    (comp (ref "U6")
      (value "ESP_WROOM_02")
      (footprint "eagle-import:ESP_WROOM_02")
      (libsource (lib "eagle-import") (part "ESP_WROOM_02"))
    )
  )
  (nets
    (net (code "1") (name "+3V3") (class "Default")
      (node (ref "3.3V") (pin "TP") (pinfunction "TP_TP") (pintype "input"))
      (node (ref "C14") (pin "1") (pinfunction "1_1") (pintype "passive"))
      (node (ref "C15") (pin "1") (pinfunction "1_1") (pintype "passive"))
      (node (ref "C6") (pin "1") (pinfunction "1_1") (pintype "passive"))
      (node (ref "R12") (pin "2") (pinfunction "2_2") (pintype "passive"))
      (node (ref "R17") (pin "2") (pinfunction "2_2") (pintype "passive"))
      (node (ref "R18") (pin "2") (pinfunction "2_2") (pintype "passive"))
      (node (ref "R23") (pin "2") (pinfunction "2_2") (pintype "passive"))
      (node (ref "R26") (pin "2") (pinfunction "2_2") (pintype "passive"))
      (node (ref "R27") (pin "2") (pinfunction "2_2") (pintype "passive"))
      (node (ref "R28") (pin "2") (pinfunction "2_2") (pintype "passive"))
      (node (ref "U3") (pin "3") (pinfunction "VDDIO_3") (pintype "power_in"))
      (node (ref "U3") (pin "7") (pinfunction "VDD_7") (pintype "power_in"))
      (node (ref "U5") (pin "5") (pinfunction "OUT_5") (pintype "passive"))
      (node (ref "U6") (pin "3V3") (pinfunction "3V3_3V3") (pintype "bidirectional"))
    )
    (net (code "2") (name "+5V") (class "Default")
      (node (ref "C18") (pin "1") (pinfunction "1_1") (pintype "passive"))
      (node (ref "C4") (pin "1") (pinfunction "1_1") (pintype "passive"))
      (node (ref "C8") (pin "1") (pinfunction "1_1") (pintype "passive"))
      (node (ref "SW1") (pin "P0") (pinfunction "P_P0") (pintype "passive"))
      (node (ref "SW1") (pin "P1") (pinfunction "P_P1") (pintype "passive"))
      (node (ref "U1") (pin "6") (pinfunction "VREGIN_6") (pintype "bidirectional"))
      (node (ref "U5") (pin "1") (pinfunction "IN_1") (pintype "input"))
      (node (ref "U5") (pin "3") (pinfunction "EN_3") (pintype "input"))
      (node (ref "U8") (pin "1") (pinfunction "VDD_1") (pintype "power_in"))
      (node (ref "U8") (pin "9") (pinfunction "VDD_9") (pintype "power_in"))
    )
    (net (code "3") (name "1ROW0") (class "Default")
      (node (ref "LED_1") (pin "2") (pinfunction "VCC_2") (pintype "bidirectional"))
      (node (ref "LED_2") (pin "2") (pinfunction "VCC_2") (pintype "bidirectional"))
      (node (ref "LED_3") (pin "2") (pinfunction "VCC_2") (pintype "bidirectional"))
      (node (ref "LED_4") (pin "2") (pinfunction "VCC_2") (pintype "bidirectional"))
      (node (ref "LED_5") (pin "2") (pinfunction "VCC_2") (pintype "bidirectional"))
      (node (ref "LED_6") (pin "2") (pinfunction "VCC_2") (pintype "bidirectional"))
      (node (ref "LED_7") (pin "2") (pinfunction "VCC_2") (pintype "bidirectional"))
      (node (ref "LED_8") (pin "2") (pinfunction "VCC_2") (pintype "bidirectional"))
      (node (ref "R2") (pin "2") (pinfunction "2_2") (pintype "passive"))
      (node (ref "U8") (pin "3") (pinfunction "OUT0_3") (pintype "output"))
    )
    (net (code "4") (name "1ROW1") (class "Default")
      (node (ref "LED_10") (pin "2") (pinfunction "VCC_2") (pintype "bidirectional"))
      (node (ref "LED_11") (pin "2") (pinfunction "VCC_2") (pintype "bidirectional"))
      (node (ref "LED_12") (pin "2") (pinfunction "VCC_2") (pintype "bidirectional"))
      (node (ref "LED_13") (pin "2") (pinfunction "VCC_2") (pintype "bidirectional"))
      (node (ref "LED_14") (pin "2") (pinfunction "VCC_2") (pintype "bidirectional"))
      (node (ref "LED_15") (pin "2") (pinfunction "VCC_2") (pintype "bidirectional"))
      (node (ref "LED_16") (pin "2") (pinfunction "VCC_2") (pintype "bidirectional"))
      (node (ref "LED_9") (pin "2") (pinfunction "VCC_2") (pintype "bidirectional"))
      (node (ref "R3") (pin "2") (pinfunction "2_2") (pintype "passive"))
      (node (ref "U8") (pin "4") (pinfunction "OUT1_4") (pintype "output"))
    )
    (net (code "5") (name "1ROW2") (class "Default")
      (node (ref "LED_17") (pin "2") (pinfunction "VCC_2") (pintype "bidirectional"))
      (node (ref "LED_18") (pin "2") (pinfunction "VCC_2") (pintype "bidirectional"))
      (node (ref "LED_19") (pin "2") (pinfunction "VCC_2") (pintype "bidirectional"))
      (node (ref "LED_20") (pin "2") (pinfunction "VCC_2") (pintype "bidirectional"))
      (node (ref "LED_21") (pin "2") (pinfunction "VCC_2") (pintype "bidirectional"))
      (node (ref "LED_22") (pin "2") (pinfunction "VCC_2") (pintype "bidirectional"))
      (node (ref "LED_23") (pin "2") (pinfunction "VCC_2") (pintype "bidirectional"))
      (node (ref "LED_24") (pin "2") (pinfunction "VCC_2") (pintype "bidirectional"))
      (node (ref "R4") (pin "2") (pinfunction "2_2") (pintype "passive"))
      (node (ref "U8") (pin "5") (pinfunction "OUT2_5") (pintype "output"))
    )
    (net (code "6") (name "1ROW3") (class "Default")
      (node (ref "LED_25") (pin "2") (pinfunction "VCC_2") (pintype "bidirectional"))
      (node (ref "LED_26") (pin "2") (pinfunction "VCC_2") (pintype "bidirectional"))
      (node (ref "LED_27") (pin "2") (pinfunction "VCC_2") (pintype "bidirectional"))
      (node (ref "LED_28") (pin "2") (pinfunction "VCC_2") (pintype "bidirectional"))
      (node (ref "LED_29") (pin "2") (pinfunction "VCC_2") (pintype "bidirectional"))
      (node (ref "LED_30") (pin "2") (pinfunction "VCC_2") (pintype "bidirectional"))
      (node (ref "LED_31") (pin "2") (pinfunction "VCC_2") (pintype "bidirectional"))
      (node (ref "LED_32") (pin "2") (pinfunction "VCC_2") (pintype "bidirectional"))
      (node (ref "R5") (pin "2") (pinfunction "2_2") (pintype "passive"))
      (node (ref "U8") (pin "6") (pinfunction "OUT3_6") (pintype "output"))
    )
    (net (code "7") (name "1ROW4") (class "Default")
      (node (ref "LED_33") (pin "2") (pinfunction "VCC_2") (pintype "bidirectional"))
      (node (ref "LED_34") (pin "2") (pinfunction "VCC_2") (pintype "bidirectional"))
      (node (ref "LED_35") (pin "2") (pinfunction "VCC_2") (pintype "bidirectional"))
      (node (ref "LED_36") (pin "2") (pinfunction "VCC_2") (pintype "bidirectional"))
      (node (ref "LED_37") (pin "2") (pinfunction "VCC_2") (pintype "bidirectional"))
      (node (ref "LED_38") (pin "2") (pinfunction "VCC_2") (pintype "bidirectional"))
      (node (ref "LED_39") (pin "2") (pinfunction "VCC_2") (pintype "bidirectional"))
      (node (ref "LED_40") (pin "2") (pinfunction "VCC_2") (pintype "bidirectional"))
      (node (ref "R13") (pin "2") (pinfunction "2_2") (pintype "passive"))
      (node (ref "U8") (pin "11") (pinfunction "OUT4_11") (pintype "output"))
    )
    (net (code "8") (name "1ROW5") (class "Default")
      (node (ref "LED_41") (pin "2") (pinfunction "VCC_2") (pintype "bidirectional"))
      (node (ref "LED_42") (pin "2") (pinfunction "VCC_2") (pintype "bidirectional"))
      (node (ref "LED_43") (pin "2") (pinfunction "VCC_2") (pintype "bidirectional"))
      (node (ref "LED_44") (pin "2") (pinfunction "VCC_2") (pintype "bidirectional"))
      (node (ref "LED_45") (pin "2") (pinfunction "VCC_2") (pintype "bidirectional"))
      (node (ref "LED_46") (pin "2") (pinfunction "VCC_2") (pintype "bidirectional"))
      (node (ref "LED_47") (pin "2") (pinfunction "VCC_2") (pintype "bidirectional"))
      (node (ref "LED_48") (pin "2") (pinfunction "VCC_2") (pintype "bidirectional"))
      (node (ref "R14") (pin "2") (pinfunction "2_2") (pintype "passive"))
      (node (ref "U8") (pin "12") (pinfunction "OUT5_12") (pintype "output"))
    )
    (net (code "9") (name "1ROW6") (class "Default")
      (node (ref "LED_49") (pin "2") (pinfunction "VCC_2") (pintype "bidirectional"))
      (node (ref "LED_50") (pin "2") (pinfunction "VCC_2") (pintype "bidirectional"))
      (node (ref "LED_51") (pin "2") (pinfunction "VCC_2") (pintype "bidirectional"))
      (node (ref "LED_52") (pin "2") (pinfunction "VCC_2") (pintype "bidirectional"))
      (node (ref "LED_53") (pin "2") (pinfunction "VCC_2") (pintype "bidirectional"))
      (node (ref "LED_54") (pin "2") (pinfunction "VCC_2") (pintype "bidirectional"))
      (node (ref "LED_55") (pin "2") (pinfunction "VCC_2") (pintype "bidirectional"))
      (node (ref "LED_56") (pin "2") (pinfunction "VCC_2") (pintype "bidirectional"))
      (node (ref "R15") (pin "2") (pinfunction "2_2") (pintype "passive"))
      (node (ref "U8") (pin "13") (pinfunction "OUT6_13") (pintype "output"))
    )
    (net (code "10") (name "1ROW7") (class "Default")
      (node (ref "LED_57") (pin "2") (pinfunction "VCC_2") (pintype "bidirectional"))
      (node (ref "LED_58") (pin "2") (pinfunction "VCC_2") (pintype "bidirectional"))
      (node (ref "LED_59") (pin "2") (pinfunction "VCC_2") (pintype "bidirectional"))
      (node (ref "LED_60") (pin "2") (pinfunction "VCC_2") (pintype "bidirectional"))
      (node (ref "LED_61") (pin "2") (pinfunction "VCC_2") (pintype "bidirectional"))
      (node (ref "LED_62") (pin "2") (pinfunction "VCC_2") (pintype "bidirectional"))
      (node (ref "LED_63") (pin "2") (pinfunction "VCC_2") (pintype "bidirectional"))
      (node (ref "LED_64") (pin "2") (pinfunction "VCC_2") (pintype "bidirectional"))
      (node (ref "R16") (pin "2") (pinfunction "2_2") (pintype "passive"))
      (node (ref "U8") (pin "14") (pinfunction "OUT7_14") (pintype "output"))
    )
    (net (code "11") (name "ADC_INT1") (class "Default")
      (node (ref "U3") (pin "5") (pinfunction "INT1_5") (pintype "power_in"))
      (node (ref "U6") (pin "IO13") (pinfunction "IO13_IO13") (pintype "bidirectional"))
    )
    (net (code "12") (name "ARM_3V3") (class "Default")
      (node (ref "C1") (pin "1") (pinfunction "1_1") (pintype "passive"))
      (node (ref "C11") (pin "1") (pinfunction "1_1") (pintype "passive"))
      (node (ref "C2") (pin "1") (pinfunction "1_1") (pintype "passive"))
      (node (ref "C3") (pin "1") (pinfunction "1_1") (pintype "passive"))
      (node (ref "C5") (pin "1") (pinfunction "1_1") (pintype "passive"))
      (node (ref "C7") (pin "1") (pinfunction "1_1") (pintype "passive"))
      (node (ref "J2") (pin "P$1") (pinfunction "VCC_P$1") (pintype "power_in"))
      (node (ref "R6") (pin "2") (pinfunction "2_2") (pintype "passive"))
      (node (ref "U1") (pin "1") (pinfunction "VDD_1") (pintype "bidirectional"))
      (node (ref "U1") (pin "11") (pinfunction "VBAT_11") (pintype "bidirectional"))
      (node (ref "U1") (pin "5") (pinfunction "VOUT33_5") (pintype "bidirectional"))
      (node (ref "U1") (pin "7") (pinfunction "VDDA_7") (pintype "bidirectional"))
      (node (ref "U2") (pin "24") (pinfunction "VCC_24") (pintype "bidirectional"))
      (node (ref "U4") (pin "24") (pinfunction "VCC_24") (pintype "bidirectional"))
    )
    (net (code "13") (name "ARM_BOOTLOADER") (class "Default")
      (node (ref "TP1") (pin "TP") (pinfunction "TP_TP") (pintype "input"))
      (node (ref "U1") (pin "25") (pinfunction "PTC4_25") (pintype "bidirectional"))
    )
    (net (code "14") (name "ARM_RESET") (class "Default")
      (node (ref "J2") (pin "P$10") (pinfunction "RESET_P$10") (pintype "bidirectional"))
      (node (ref "U1") (pin "19") (pinfunction "RESET_B_19") (pintype "bidirectional"))
    )
    (net (code "15") (name "ARM_RX") (class "Default")
      (node (ref "J2") (pin "P$8") (pinfunction "TDI_P$8") (pintype "bidirectional"))
      (node (ref "U1") (pin "13") (pinfunction "PTA1_13") (pintype "bidirectional"))
      (node (ref "U6") (pin "TXD") (pinfunction "TXD_TXD") (pintype "bidirectional"))
    )
    (net (code "16") (name "ARM_RX1") (class "Default")
      (node (ref "R12") (pin "1") (pinfunction "1_1") (pintype "passive"))
      (node (ref "U1") (pin "24") (pinfunction "PTC3_24") (pintype "bidirectional"))
      (node (ref "U6") (pin "IO2") (pinfunction "IO2_IO2") (pintype "bidirectional"))
    )
    (net (code "17") (name "ARM_TCK") (class "Default")
      (node (ref "J2") (pin "P$4") (pinfunction "TCK_P$4") (pintype "bidirectional"))
      (node (ref "U1") (pin "12") (pinfunction "PTA0_12") (pintype "bidirectional"))
    )
    (net (code "18") (name "ARM_TMS") (class "Default")
      (node (ref "J2") (pin "P$2") (pinfunction "TMS_P$2") (pintype "bidirectional"))
      (node (ref "U1") (pin "15") (pinfunction "PTA3_15") (pintype "bidirectional"))
    )
    (net (code "19") (name "ARM_TX") (class "Default")
      (node (ref "J2") (pin "P$6") (pinfunction "TDO_P$6") (pintype "bidirectional"))
      (node (ref "U1") (pin "14") (pinfunction "PTA2_14") (pintype "bidirectional"))
      (node (ref "U6") (pin "RXD") (pinfunction "RXD_RXD") (pintype "bidirectional"))
    )
    (net (code "20") (name "BCOL0") (class "Default")
      (node (ref "LED_1") (pin "3") (pinfunction "BLUE_3") (pintype "bidirectional"))
      (node (ref "LED_17") (pin "3") (pinfunction "BLUE_3") (pintype "bidirectional"))
      (node (ref "LED_25") (pin "3") (pinfunction "BLUE_3") (pintype "bidirectional"))
      (node (ref "LED_33") (pin "3") (pinfunction "BLUE_3") (pintype "bidirectional"))
      (node (ref "LED_41") (pin "3") (pinfunction "BLUE_3") (pintype "bidirectional"))
      (node (ref "LED_49") (pin "3") (pinfunction "BLUE_3") (pintype "bidirectional"))
      (node (ref "LED_57") (pin "3") (pinfunction "BLUE_3") (pintype "bidirectional"))
      (node (ref "LED_9") (pin "3") (pinfunction "BLUE_3") (pintype "bidirectional"))
      (node (ref "U2") (pin "13") (pinfunction "OUT8_13") (pintype "bidirectional"))
    )
    (net (code "21") (name "BCOL1") (class "Default")
      (node (ref "LED_10") (pin "3") (pinfunction "BLUE_3") (pintype "bidirectional"))
      (node (ref "LED_18") (pin "3") (pinfunction "BLUE_3") (pintype "bidirectional"))
      (node (ref "LED_2") (pin "3") (pinfunction "BLUE_3") (pintype "bidirectional"))
      (node (ref "LED_26") (pin "3") (pinfunction "BLUE_3") (pintype "bidirectional"))
      (node (ref "LED_34") (pin "3") (pinfunction "BLUE_3") (pintype "bidirectional"))
      (node (ref "LED_42") (pin "3") (pinfunction "BLUE_3") (pintype "bidirectional"))
      (node (ref "LED_50") (pin "3") (pinfunction "BLUE_3") (pintype "bidirectional"))
      (node (ref "LED_58") (pin "3") (pinfunction "BLUE_3") (pintype "bidirectional"))
      (node (ref "U2") (pin "14") (pinfunction "OUT9_14") (pintype "bidirectional"))
    )
    (net (code "22") (name "BCOL2") (class "Default")
      (node (ref "LED_11") (pin "3") (pinfunction "BLUE_3") (pintype "bidirectional"))
      (node (ref "LED_19") (pin "3") (pinfunction "BLUE_3") (pintype "bidirectional"))
      (node (ref "LED_27") (pin "3") (pinfunction "BLUE_3") (pintype "bidirectional"))
      (node (ref "LED_3") (pin "3") (pinfunction "BLUE_3") (pintype "bidirectional"))
      (node (ref "LED_35") (pin "3") (pinfunction "BLUE_3") (pintype "bidirectional"))
      (node (ref "LED_43") (pin "3") (pinfunction "BLUE_3") (pintype "bidirectional"))
      (node (ref "LED_51") (pin "3") (pinfunction "BLUE_3") (pintype "bidirectional"))
      (node (ref "LED_59") (pin "3") (pinfunction "BLUE_3") (pintype "bidirectional"))
      (node (ref "U2") (pin "15") (pinfunction "OUT10_15") (pintype "bidirectional"))
    )
    (net (code "23") (name "BCOL3") (class "Default")
      (node (ref "LED_12") (pin "3") (pinfunction "BLUE_3") (pintype "bidirectional"))
      (node (ref "LED_20") (pin "3") (pinfunction "BLUE_3") (pintype "bidirectional"))
      (node (ref "LED_28") (pin "3") (pinfunction "BLUE_3") (pintype "bidirectional"))
      (node (ref "LED_36") (pin "3") (pinfunction "BLUE_3") (pintype "bidirectional"))
      (node (ref "LED_4") (pin "3") (pinfunction "BLUE_3") (pintype "bidirectional"))
      (node (ref "LED_44") (pin "3") (pinfunction "BLUE_3") (pintype "bidirectional"))
      (node (ref "LED_52") (pin "3") (pinfunction "BLUE_3") (pintype "bidirectional"))
      (node (ref "LED_60") (pin "3") (pinfunction "BLUE_3") (pintype "bidirectional"))
      (node (ref "U2") (pin "16") (pinfunction "OUT11_16") (pintype "bidirectional"))
    )
    (net (code "24") (name "BCOL4") (class "Default")
      (node (ref "LED_13") (pin "3") (pinfunction "BLUE_3") (pintype "bidirectional"))
      (node (ref "LED_21") (pin "3") (pinfunction "BLUE_3") (pintype "bidirectional"))
      (node (ref "LED_29") (pin "3") (pinfunction "BLUE_3") (pintype "bidirectional"))
      (node (ref "LED_37") (pin "3") (pinfunction "BLUE_3") (pintype "bidirectional"))
      (node (ref "LED_45") (pin "3") (pinfunction "BLUE_3") (pintype "bidirectional"))
      (node (ref "LED_5") (pin "3") (pinfunction "BLUE_3") (pintype "bidirectional"))
      (node (ref "LED_53") (pin "3") (pinfunction "BLUE_3") (pintype "bidirectional"))
      (node (ref "LED_61") (pin "3") (pinfunction "BLUE_3") (pintype "bidirectional"))
      (node (ref "U2") (pin "17") (pinfunction "OUT12_17") (pintype "bidirectional"))
    )
    (net (code "25") (name "BCOL5") (class "Default")
      (node (ref "LED_14") (pin "3") (pinfunction "BLUE_3") (pintype "bidirectional"))
      (node (ref "LED_22") (pin "3") (pinfunction "BLUE_3") (pintype "bidirectional"))
      (node (ref "LED_30") (pin "3") (pinfunction "BLUE_3") (pintype "bidirectional"))
      (node (ref "LED_38") (pin "3") (pinfunction "BLUE_3") (pintype "bidirectional"))
      (node (ref "LED_46") (pin "3") (pinfunction "BLUE_3") (pintype "bidirectional"))
      (node (ref "LED_54") (pin "3") (pinfunction "BLUE_3") (pintype "bidirectional"))
      (node (ref "LED_6") (pin "3") (pinfunction "BLUE_3") (pintype "bidirectional"))
      (node (ref "LED_62") (pin "3") (pinfunction "BLUE_3") (pintype "bidirectional"))
      (node (ref "U2") (pin "18") (pinfunction "OUT13_18") (pintype "bidirectional"))
    )
    (net (code "26") (name "BCOL6") (class "Default")
      (node (ref "LED_15") (pin "3") (pinfunction "BLUE_3") (pintype "bidirectional"))
      (node (ref "LED_23") (pin "3") (pinfunction "BLUE_3") (pintype "bidirectional"))
      (node (ref "LED_31") (pin "3") (pinfunction "BLUE_3") (pintype "bidirectional"))
      (node (ref "LED_39") (pin "3") (pinfunction "BLUE_3") (pintype "bidirectional"))
      (node (ref "LED_47") (pin "3") (pinfunction "BLUE_3") (pintype "bidirectional"))
      (node (ref "LED_55") (pin "3") (pinfunction "BLUE_3") (pintype "bidirectional"))
      (node (ref "LED_63") (pin "3") (pinfunction "BLUE_3") (pintype "bidirectional"))
      (node (ref "LED_7") (pin "3") (pinfunction "BLUE_3") (pintype "bidirectional"))
      (node (ref "U2") (pin "19") (pinfunction "OUT14_19") (pintype "bidirectional"))
    )
    (net (code "27") (name "BCOL7") (class "Default")
      (node (ref "LED_16") (pin "3") (pinfunction "BLUE_3") (pintype "bidirectional"))
      (node (ref "LED_24") (pin "3") (pinfunction "BLUE_3") (pintype "bidirectional"))
      (node (ref "LED_32") (pin "3") (pinfunction "BLUE_3") (pintype "bidirectional"))
      (node (ref "LED_40") (pin "3") (pinfunction "BLUE_3") (pintype "bidirectional"))
      (node (ref "LED_48") (pin "3") (pinfunction "BLUE_3") (pintype "bidirectional"))
      (node (ref "LED_56") (pin "3") (pinfunction "BLUE_3") (pintype "bidirectional"))
      (node (ref "LED_64") (pin "3") (pinfunction "BLUE_3") (pintype "bidirectional"))
      (node (ref "LED_8") (pin "3") (pinfunction "BLUE_3") (pintype "bidirectional"))
      (node (ref "U2") (pin "20") (pinfunction "OUT15_20") (pintype "bidirectional"))
    )
    (net (code "28") (name "BOOST_5V") (class "Default")
      (node (ref "C9") (pin "1") (pinfunction "1_1") (pintype "passive"))
      (node (ref "D2") (pin "A") (pinfunction "A_A") (pintype "passive"))
      (node (ref "U7") (pin "8") (pinfunction "OUT_8") (pintype "bidirectional"))
    )
    (net (code "29") (name "BUTTON1") (class "Default")
      (node (ref "R28") (pin "1") (pinfunction "1_1") (pintype "passive"))
      (node (ref "SW2") (pin "1") (pinfunction "P_1") (pintype "passive"))
      (node (ref "SW2") (pin "2") (pinfunction "P_2") (pintype "passive"))
      (node (ref "U6") (pin "IO4") (pinfunction "IO4_IO4") (pintype "bidirectional"))
    )
    (net (code "30") (name "CHARGE") (class "Default")
      (node (ref "D1") (pin "A") (pinfunction "A_A") (pintype "passive"))
      (node (ref "U7") (pin "6") (pinfunction "LED2_6") (pintype "bidirectional"))
    )
    (net (code "31") (name "DISCHARGE") (class "Default")
      (node (ref "D4") (pin "A") (pinfunction "A_A") (pintype "passive"))
      (node (ref "U7") (pin "5") (pinfunction "LED1_5") (pintype "bidirectional"))
    )
    (net (code "32") (name "ESP_GPIO0") (class "Default")
      (node (ref "R23") (pin "1") (pinfunction "1_1") (pintype "passive"))
      (node (ref "U1") (pin "21") (pinfunction "PTB1_21") (pintype "bidirectional"))
      (node (ref "U6") (pin "IO0") (pinfunction "IO0_IO0") (pintype "bidirectional"))
    )
    (net (code "33") (name "ESP_GPIO15") (class "Default")
      (node (ref "R25") (pin "2") (pinfunction "2_2") (pintype "passive"))
      (node (ref "U6") (pin "IO15") (pinfunction "IO15_IO15") (pintype "bidirectional"))
    )
    (net (code "34") (name "ESP_GPIO16") (class "Default")
      (node (ref "16") (pin "TP") (pinfunction "TP_TP") (pintype "input"))
      (node (ref "U6") (pin "IO18") (pinfunction "IO18_IO18") (pintype "bidirectional"))
    )
    (net (code "35") (name "ESP_RESET") (class "Default")
      (node (ref "R27") (pin "1") (pinfunction "1_1") (pintype "passive"))
      (node (ref "U1") (pin "20") (pinfunction "PTB0_20") (pintype "bidirectional"))
      (node (ref "U6") (pin "RST") (pinfunction "RST_RST") (pintype "bidirectional"))
    )
    (net (code "36") (name "ESP_TOUT") (class "Default")
      (node (ref "ANALOG_IN") (pin "TP") (pinfunction "TP_TP") (pintype "input"))
      (node (ref "U6") (pin "TOUT") (pinfunction "TOUT_TOUT") (pintype "bidirectional"))
    )
    (net (code "37") (name "EXP_GPIO5") (class "Default")
      (node (ref "5") (pin "TP") (pinfunction "TP_TP") (pintype "input"))
      (node (ref "U6") (pin "IO5") (pinfunction "IO5_IO5") (pintype "bidirectional"))
    )
    (net (code "38") (name "GCOL0") (class "Default")
      (node (ref "LED_1") (pin "4") (pinfunction "GREEN_4") (pintype "bidirectional"))
      (node (ref "LED_17") (pin "4") (pinfunction "GREEN_4") (pintype "bidirectional"))
      (node (ref "LED_25") (pin "4") (pinfunction "GREEN_4") (pintype "bidirectional"))
      (node (ref "LED_33") (pin "4") (pinfunction "GREEN_4") (pintype "bidirectional"))
      (node (ref "LED_41") (pin "4") (pinfunction "GREEN_4") (pintype "bidirectional"))
      (node (ref "LED_49") (pin "4") (pinfunction "GREEN_4") (pintype "bidirectional"))
      (node (ref "LED_57") (pin "4") (pinfunction "GREEN_4") (pintype "bidirectional"))
      (node (ref "LED_9") (pin "4") (pinfunction "GREEN_4") (pintype "bidirectional"))
      (node (ref "U4") (pin "5") (pinfunction "OUT0_5") (pintype "bidirectional"))
    )
    (net (code "39") (name "GCOL1") (class "Default")
      (node (ref "LED_10") (pin "4") (pinfunction "GREEN_4") (pintype "bidirectional"))
      (node (ref "LED_18") (pin "4") (pinfunction "GREEN_4") (pintype "bidirectional"))
      (node (ref "LED_2") (pin "4") (pinfunction "GREEN_4") (pintype "bidirectional"))
      (node (ref "LED_26") (pin "4") (pinfunction "GREEN_4") (pintype "bidirectional"))
      (node (ref "LED_34") (pin "4") (pinfunction "GREEN_4") (pintype "bidirectional"))
      (node (ref "LED_42") (pin "4") (pinfunction "GREEN_4") (pintype "bidirectional"))
      (node (ref "LED_50") (pin "4") (pinfunction "GREEN_4") (pintype "bidirectional"))
      (node (ref "LED_58") (pin "4") (pinfunction "GREEN_4") (pintype "bidirectional"))
      (node (ref "U4") (pin "6") (pinfunction "OUT1_6") (pintype "bidirectional"))
    )
    (net (code "40") (name "GCOL2") (class "Default")
      (node (ref "LED_11") (pin "4") (pinfunction "GREEN_4") (pintype "bidirectional"))
      (node (ref "LED_19") (pin "4") (pinfunction "GREEN_4") (pintype "bidirectional"))
      (node (ref "LED_27") (pin "4") (pinfunction "GREEN_4") (pintype "bidirectional"))
      (node (ref "LED_3") (pin "4") (pinfunction "GREEN_4") (pintype "bidirectional"))
      (node (ref "LED_35") (pin "4") (pinfunction "GREEN_4") (pintype "bidirectional"))
      (node (ref "LED_43") (pin "4") (pinfunction "GREEN_4") (pintype "bidirectional"))
      (node (ref "LED_51") (pin "4") (pinfunction "GREEN_4") (pintype "bidirectional"))
      (node (ref "LED_59") (pin "4") (pinfunction "GREEN_4") (pintype "bidirectional"))
      (node (ref "U4") (pin "7") (pinfunction "OUT2_7") (pintype "bidirectional"))
    )
    (net (code "41") (name "GCOL3") (class "Default")
      (node (ref "LED_12") (pin "4") (pinfunction "GREEN_4") (pintype "bidirectional"))
      (node (ref "LED_20") (pin "4") (pinfunction "GREEN_4") (pintype "bidirectional"))
      (node (ref "LED_28") (pin "4") (pinfunction "GREEN_4") (pintype "bidirectional"))
      (node (ref "LED_36") (pin "4") (pinfunction "GREEN_4") (pintype "bidirectional"))
      (node (ref "LED_4") (pin "4") (pinfunction "GREEN_4") (pintype "bidirectional"))
      (node (ref "LED_44") (pin "4") (pinfunction "GREEN_4") (pintype "bidirectional"))
      (node (ref "LED_52") (pin "4") (pinfunction "GREEN_4") (pintype "bidirectional"))
      (node (ref "LED_60") (pin "4") (pinfunction "GREEN_4") (pintype "bidirectional"))
      (node (ref "U4") (pin "8") (pinfunction "OUT3_8") (pintype "bidirectional"))
    )
    (net (code "42") (name "GCOL4") (class "Default")
      (node (ref "LED_13") (pin "4") (pinfunction "GREEN_4") (pintype "bidirectional"))
      (node (ref "LED_21") (pin "4") (pinfunction "GREEN_4") (pintype "bidirectional"))
      (node (ref "LED_29") (pin "4") (pinfunction "GREEN_4") (pintype "bidirectional"))
      (node (ref "LED_37") (pin "4") (pinfunction "GREEN_4") (pintype "bidirectional"))
      (node (ref "LED_45") (pin "4") (pinfunction "GREEN_4") (pintype "bidirectional"))
      (node (ref "LED_5") (pin "4") (pinfunction "GREEN_4") (pintype "bidirectional"))
      (node (ref "LED_53") (pin "4") (pinfunction "GREEN_4") (pintype "bidirectional"))
      (node (ref "LED_61") (pin "4") (pinfunction "GREEN_4") (pintype "bidirectional"))
      (node (ref "U4") (pin "9") (pinfunction "OUT4_9") (pintype "bidirectional"))
    )
    (net (code "43") (name "GCOL5") (class "Default")
      (node (ref "LED_14") (pin "4") (pinfunction "GREEN_4") (pintype "bidirectional"))
      (node (ref "LED_22") (pin "4") (pinfunction "GREEN_4") (pintype "bidirectional"))
      (node (ref "LED_30") (pin "4") (pinfunction "GREEN_4") (pintype "bidirectional"))
      (node (ref "LED_38") (pin "4") (pinfunction "GREEN_4") (pintype "bidirectional"))
      (node (ref "LED_46") (pin "4") (pinfunction "GREEN_4") (pintype "bidirectional"))
      (node (ref "LED_54") (pin "4") (pinfunction "GREEN_4") (pintype "bidirectional"))
      (node (ref "LED_6") (pin "4") (pinfunction "GREEN_4") (pintype "bidirectional"))
      (node (ref "LED_62") (pin "4") (pinfunction "GREEN_4") (pintype "bidirectional"))
      (node (ref "U4") (pin "10") (pinfunction "OUT5_10") (pintype "bidirectional"))
    )
    (net (code "44") (name "GCOL6") (class "Default")
      (node (ref "LED_15") (pin "4") (pinfunction "GREEN_4") (pintype "bidirectional"))
      (node (ref "LED_23") (pin "4") (pinfunction "GREEN_4") (pintype "bidirectional"))
      (node (ref "LED_31") (pin "4") (pinfunction "GREEN_4") (pintype "bidirectional"))
      (node (ref "LED_39") (pin "4") (pinfunction "GREEN_4") (pintype "bidirectional"))
      (node (ref "LED_47") (pin "4") (pinfunction "GREEN_4") (pintype "bidirectional"))
      (node (ref "LED_55") (pin "4") (pinfunction "GREEN_4") (pintype "bidirectional"))
      (node (ref "LED_63") (pin "4") (pinfunction "GREEN_4") (pintype "bidirectional"))
      (node (ref "LED_7") (pin "4") (pinfunction "GREEN_4") (pintype "bidirectional"))
      (node (ref "U4") (pin "11") (pinfunction "OUT6_11") (pintype "bidirectional"))
    )
    (net (code "45") (name "GCOL7") (class "Default")
      (node (ref "LED_16") (pin "4") (pinfunction "GREEN_4") (pintype "bidirectional"))
      (node (ref "LED_24") (pin "4") (pinfunction "GREEN_4") (pintype "bidirectional"))
      (node (ref "LED_32") (pin "4") (pinfunction "GREEN_4") (pintype "bidirectional"))
      (node (ref "LED_40") (pin "4") (pinfunction "GREEN_4") (pintype "bidirectional"))
      (node (ref "LED_48") (pin "4") (pinfunction "GREEN_4") (pintype "bidirectional"))
      (node (ref "LED_56") (pin "4") (pinfunction "GREEN_4") (pintype "bidirectional"))
      (node (ref "LED_64") (pin "4") (pinfunction "GREEN_4") (pintype "bidirectional"))
      (node (ref "LED_8") (pin "4") (pinfunction "GREEN_4") (pintype "bidirectional"))
      (node (ref "U4") (pin "12") (pinfunction "OUT7_12") (pintype "bidirectional"))
    )
    (net (code "46") (name "GND") (class "Default")
      (node (ref "C1") (pin "2") (pinfunction "2_2") (pintype "passive"))
      (node (ref "C10") (pin "2") (pinfunction "2_2") (pintype "passive"))
      (node (ref "C11") (pin "2") (pinfunction "2_2") (pintype "passive"))
      (node (ref "C12") (pin "2") (pinfunction "2_2") (pintype "passive"))
      (node (ref "C14") (pin "2") (pinfunction "2_2") (pintype "passive"))
      (node (ref "C15") (pin "2") (pinfunction "2_2") (pintype "passive"))
      (node (ref "C16") (pin "2") (pinfunction "2_2") (pintype "passive"))
      (node (ref "C17") (pin "2") (pinfunction "2_2") (pintype "passive"))
      (node (ref "C18") (pin "2") (pinfunction "2_2") (pintype "passive"))
      (node (ref "C2") (pin "2") (pinfunction "2_2") (pintype "passive"))
      (node (ref "C3") (pin "2") (pinfunction "2_2") (pintype "passive"))
      (node (ref "C4") (pin "2") (pinfunction "2_2") (pintype "passive"))
      (node (ref "C5") (pin "2") (pinfunction "2_2") (pintype "passive"))
      (node (ref "C6") (pin "2") (pinfunction "2_2") (pintype "passive"))
      (node (ref "C7") (pin "2") (pinfunction "2_2") (pintype "passive"))
      (node (ref "C8") (pin "2") (pinfunction "2_2") (pintype "passive"))
      (node (ref "C9") (pin "2") (pinfunction "2_2") (pintype "passive"))
      (node (ref "D1") (pin "C") (pinfunction "C_C") (pintype "passive"))
      (node (ref "D4") (pin "C") (pinfunction "C_C") (pintype "passive"))
      (node (ref "GROUND") (pin "TP") (pinfunction "TP_TP") (pintype "input"))
      (node (ref "J1") (pin "PIN$5") (pinfunction "GND_PIN$5") (pintype "bidirectional"))
      (node (ref "J2") (pin "P$3") (pinfunction "GND_P$3") (pintype "power_in"))
      (node (ref "J2") (pin "P$5") (pinfunction "GND_P$5") (pintype "power_in"))
      (node (ref "J2") (pin "P$9") (pinfunction "GND_P$9") (pintype "power_in"))
      (node (ref "J3") (pin "-") (pinfunction "-_-") (pintype "bidirectional"))
      (node (ref "L2") (pin "2") (pinfunction "P$2_2") (pintype "bidirectional"))
      (node (ref "Q1") (pin "P$2") (pinfunction "P$1_P$2") (pintype "bidirectional"))
      (node (ref "Q1") (pin "P$4") (pinfunction "P$1_P$4") (pintype "bidirectional"))
      (node (ref "R1") (pin "1") (pinfunction "1_1") (pintype "passive"))
      (node (ref "R11") (pin "1") (pinfunction "1_1") (pintype "passive"))
      (node (ref "R13") (pin "1") (pinfunction "1_1") (pintype "passive"))
      (node (ref "R14") (pin "1") (pinfunction "1_1") (pintype "passive"))
      (node (ref "R15") (pin "1") (pinfunction "1_1") (pintype "passive"))
      (node (ref "R16") (pin "1") (pinfunction "1_1") (pintype "passive"))
      (node (ref "R2") (pin "1") (pinfunction "1_1") (pintype "passive"))
      (node (ref "R21") (pin "1") (pinfunction "1_1") (pintype "passive"))
      (node (ref "R25") (pin "1") (pinfunction "1_1") (pintype "passive"))
      (node (ref "R3") (pin "1") (pinfunction "1_1") (pintype "passive"))
      (node (ref "R4") (pin "1") (pinfunction "1_1") (pintype "passive"))
      (node (ref "R5") (pin "1") (pinfunction "1_1") (pintype "passive"))
      (node (ref "R9") (pin "1") (pinfunction "1_1") (pintype "passive"))
      (node (ref "SW2") (pin "3") (pinfunction "S_3") (pintype "passive"))
      (node (ref "SW2") (pin "4") (pinfunction "S_4") (pintype "passive"))
      (node (ref "SW2") (pin "5") (pinfunction "SHIELD_5") (pintype "passive"))
      (node (ref "U1") (pin "2") (pinfunction "VSS_2") (pintype "bidirectional"))
      (node (ref "U1") (pin "8") (pinfunction "VSSA_8") (pintype "bidirectional"))
      (node (ref "U1") (pin "PAD@1") (pinfunction "VSS_PAD@1") (pintype "bidirectional"))
      (node (ref "U1") (pin "PAD@11") (pinfunction "VSS_PAD@11") (pintype "bidirectional"))
      (node (ref "U1") (pin "PAD@4") (pinfunction "VSS_PAD@4") (pintype "bidirectional"))
      (node (ref "U1") (pin "PAD@9") (pinfunction "VSS_PAD@9") (pintype "bidirectional"))
      (node (ref "U2") (pin "1") (pinfunction "GND_1") (pintype "bidirectional"))
      (node (ref "U3") (pin "1") (pinfunction "AD0_1") (pintype "power_in"))
      (node (ref "U3") (pin "4") (pinfunction "GND_4") (pintype "power_in"))
      (node (ref "U3") (pin "8") (pinfunction "GND_8") (pintype "power_in"))
      (node (ref "U3") (pin "9") (pinfunction "GND_9") (pintype "power_in"))
      (node (ref "U4") (pin "1") (pinfunction "GND_1") (pintype "bidirectional"))
      (node (ref "U5") (pin "2") (pinfunction "GND_2") (pintype "input"))
      (node (ref "U6") (pin "GND$1") (pinfunction "GND_GND$1") (pintype "bidirectional"))
      (node (ref "U6") (pin "GND$2") (pinfunction "GND_GND$2") (pintype "bidirectional"))
      (node (ref "U6") (pin "GND$3") (pinfunction "GND_GND$3") (pintype "bidirectional"))
      (node (ref "U7") (pin "2") (pinfunction "PGND_2") (pintype "bidirectional"))
      (node (ref "U7") (pin "7") (pinfunction "GND_7") (pintype "bidirectional"))
      (node (ref "U8") (pin "8") (pinfunction "GND_8") (pintype "power_in"))
      (node (ref "Z1") (pin "1") (pinfunction "1_1") (pintype "passive"))
      (node (ref "Z2") (pin "1") (pinfunction "1_1") (pintype "passive"))
    )
    (net (code "47") (name "I2C_SCL") (class "Default")
      (node (ref "R18") (pin "1") (pinfunction "1_1") (pintype "passive"))
      (node (ref "U3") (pin "12") (pinfunction "SCL_12") (pintype "power_in"))
      (node (ref "U6") (pin "IO14") (pinfunction "IO14_IO14") (pintype "bidirectional"))
    )
    (net (code "48") (name "I2C_SDA") (class "Default")
      (node (ref "R17") (pin "1") (pinfunction "1_1") (pintype "passive"))
      (node (ref "U3") (pin "2") (pinfunction "SDA_2") (pintype "power_in"))
      (node (ref "U6") (pin "IO12") (pinfunction "IO12_IO12") (pintype "bidirectional"))
    )
    (net (code "49") (name "INT2") (class "Default")
      (node (ref "U3") (pin "6") (pinfunction "INT2_6") (pintype "power_in"))
    )
    (net (code "50") (name "LED_CLK") (class "Default")
      (node (ref "U1") (pin "26") (pinfunction "PTC5_26") (pintype "bidirectional"))
      (node (ref "U2") (pin "3") (pinfunction "CLK_3") (pintype "bidirectional"))
      (node (ref "U4") (pin "3") (pinfunction "CLK_3") (pintype "bidirectional"))
    )
    (net (code "51") (name "LED_DAT_0") (class "Default")
      (node (ref "U1") (pin "27") (pinfunction "PTC6_27") (pintype "bidirectional"))
      (node (ref "U2") (pin "2") (pinfunction "DIN_2") (pintype "bidirectional"))
    )
    (net (code "52") (name "LED_DAT_1") (class "Default")
      (node (ref "U2") (pin "22") (pinfunction "DOUT_22") (pintype "bidirectional"))
      (node (ref "U4") (pin "2") (pinfunction "DIN_2") (pintype "bidirectional"))
    )
    (net (code "53") (name "LED_HS_EN") (class "Default")
      (node (ref "R21") (pin "2") (pinfunction "2_2") (pintype "passive"))
      (node (ref "U1") (pin "22") (pinfunction "PTC1_22") (pintype "bidirectional"))
      (node (ref "U8") (pin "7") (pinfunction "E1_7") (pintype "input"))
    )
    (net (code "54") (name "LED_OE") (class "Default")
      (node (ref "R6") (pin "1") (pinfunction "1_1") (pintype "passive"))
      (node (ref "U1") (pin "16") (pinfunction "PTA4_16") (pintype "bidirectional"))
      (node (ref "U2") (pin "21") (pinfunction "OE_21") (pintype "bidirectional"))
      (node (ref "U4") (pin "21") (pinfunction "OE_21") (pintype "bidirectional"))
      (node (ref "U8") (pin "10") (pinfunction "E2_10") (pintype "input"))
    )
    (net (code "55") (name "LED_ROW_A") (class "Default")
      (node (ref "U1") (pin "30") (pinfunction "PTD5_30") (pintype "bidirectional"))
      (node (ref "U8") (pin "15") (pinfunction "A0_15") (pintype "input"))
    )
    (net (code "56") (name "LED_ROW_B") (class "Default")
      (node (ref "U1") (pin "31") (pinfunction "PTD6_31") (pintype "bidirectional"))
      (node (ref "U8") (pin "16") (pinfunction "A1_16") (pintype "input"))
    )
    (net (code "57") (name "LED_ROW_C") (class "Default")
      (node (ref "U1") (pin "32") (pinfunction "PTD7_32") (pintype "bidirectional"))
      (node (ref "U8") (pin "2") (pinfunction "A2_2") (pintype "input"))
    )
    (net (code "58") (name "LED_STB") (class "Default")
      (node (ref "U1") (pin "29") (pinfunction "PTD4_29") (pintype "bidirectional"))
      (node (ref "U2") (pin "4") (pinfunction "LATCH_4") (pintype "bidirectional"))
      (node (ref "U4") (pin "4") (pinfunction "LATCH_4") (pintype "bidirectional"))
    )
    (net (code "59") (name "Net-(C10-Pad1)") (class "Default")
      (node (ref "C10") (pin "1") (pinfunction "1_1") (pintype "passive"))
      (node (ref "R10") (pin "2") (pinfunction "2_2") (pintype "passive"))
    )
    (net (code "60") (name "Net-(D2-PadC)") (class "Default")
      (node (ref "D2") (pin "C") (pinfunction "C_C") (pintype "passive"))
      (node (ref "D3") (pin "C") (pinfunction "C_C") (pintype "passive"))
      (node (ref "SW1") (pin "S0") (pinfunction "S_S0") (pintype "passive"))
      (node (ref "SW1") (pin "S1") (pinfunction "S_S1") (pintype "passive"))
    )
    (net (code "61") (name "Net-(J1-D+)") (class "Default")
      (node (ref "J1") (pin "PIN$3") (pinfunction "D+_PIN$3") (pintype "bidirectional"))
      (node (ref "R8") (pin "1") (pinfunction "1_1") (pintype "passive"))
      (node (ref "Z2") (pin "2") (pinfunction "2_2") (pintype "passive"))
    )
    (net (code "62") (name "Net-(J1-D-)") (class "Default")
      (node (ref "J1") (pin "PIN$2") (pinfunction "D-_PIN$2") (pintype "bidirectional"))
      (node (ref "R7") (pin "1") (pinfunction "1_1") (pintype "passive"))
      (node (ref "Z1") (pin "2") (pinfunction "2_2") (pintype "passive"))
    )
    (net (code "63") (name "Net-(L1-2)") (class "Default")
      (node (ref "L1") (pin "P$2") (pinfunction "2_P$2") (pintype "passive"))
      (node (ref "R10") (pin "1") (pinfunction "1_1") (pintype "passive"))
      (node (ref "U7") (pin "1") (pinfunction "LX_1") (pintype "bidirectional"))
    )
    (net (code "64") (name "Net-(L2-P$1)") (class "Default")
      (node (ref "J1") (pin "PAD$1") (pinfunction "SHIELD_PAD$1") (pintype "bidirectional"))
      (node (ref "J1") (pin "PAD$10") (pinfunction "SHIELD_PAD$10") (pintype "bidirectional"))
      (node (ref "J1") (pin "PAD$2") (pinfunction "SHIELD_PAD$2") (pintype "bidirectional"))
      (node (ref "J1") (pin "PAD$3") (pinfunction "SHIELD_PAD$3") (pintype "bidirectional"))
      (node (ref "J1") (pin "PAD$4") (pinfunction "SHIELD_PAD$4") (pintype "bidirectional"))
      (node (ref "J1") (pin "PAD$5") (pinfunction "SHIELD_PAD$5") (pintype "bidirectional"))
      (node (ref "J1") (pin "PAD$6") (pinfunction "SHIELD_PAD$6") (pintype "bidirectional"))
      (node (ref "J1") (pin "PAD$7") (pinfunction "SHIELD_PAD$7") (pintype "bidirectional"))
      (node (ref "J1") (pin "PAD$8") (pinfunction "SHIELD_PAD$8") (pintype "bidirectional"))
      (node (ref "J1") (pin "PAD$9") (pinfunction "SHIELD_PAD$9") (pintype "bidirectional"))
      (node (ref "L2") (pin "1") (pinfunction "P$1_1") (pintype "bidirectional"))
    )
    (net (code "65") (name "Net-(Q1-1)") (class "Default")
      (node (ref "Q1") (pin "P$1") (pinfunction "1_P$1") (pintype "passive"))
      (node (ref "U1") (pin "18") (pinfunction "PTA19_18") (pintype "bidirectional"))
    )
    (net (code "66") (name "Net-(Q1-2)") (class "Default")
      (node (ref "Q1") (pin "P$3") (pinfunction "2_P$3") (pintype "passive"))
      (node (ref "U1") (pin "17") (pinfunction "PTA18_17") (pintype "bidirectional"))
    )
    (net (code "67") (name "Net-(R11-Pad2)") (class "Default")
      (node (ref "R11") (pin "2") (pinfunction "2_2") (pintype "passive"))
      (node (ref "SW1") (pin "O0") (pinfunction "O_O0") (pintype "passive"))
      (node (ref "SW1") (pin "O1") (pinfunction "O_O1") (pintype "passive"))
    )
    (net (code "68") (name "Net-(R19B-1)") (class "Default")
      (node (ref "R19") (pin "2") (pinfunction "1_2") (pintype "passive"))
      (node (ref "U2") (pin "7") (pinfunction "OUT2_7") (pintype "bidirectional"))
    )
    (net (code "69") (name "Net-(R19C-1)") (class "Default")
      (node (ref "R19") (pin "3") (pinfunction "1_3") (pintype "passive"))
      (node (ref "U2") (pin "6") (pinfunction "OUT1_6") (pintype "bidirectional"))
    )
    (net (code "70") (name "Net-(R19D-1)") (class "Default")
      (node (ref "R19") (pin "4") (pinfunction "1_4") (pintype "passive"))
      (node (ref "U2") (pin "5") (pinfunction "OUT0_5") (pintype "bidirectional"))
    )
    (net (code "71") (name "Net-(R20B-1)") (class "Default")
      (node (ref "R20") (pin "2") (pinfunction "1_2") (pintype "passive"))
      (node (ref "U2") (pin "11") (pinfunction "OUT6_11") (pintype "bidirectional"))
    )
    (net (code "72") (name "Net-(R20C-1)") (class "Default")
      (node (ref "R20") (pin "3") (pinfunction "1_3") (pintype "passive"))
      (node (ref "U2") (pin "10") (pinfunction "OUT5_10") (pintype "bidirectional"))
    )
    (net (code "73") (name "Net-(R20D-1)") (class "Default")
      (node (ref "R20") (pin "4") (pinfunction "1_4") (pintype "passive"))
      (node (ref "U2") (pin "9") (pinfunction "OUT4_9") (pintype "bidirectional"))
    )
    (net (code "74") (name "Net-(R26-Pad1)") (class "Default")
      (node (ref "R26") (pin "1") (pinfunction "1_1") (pintype "passive"))
      (node (ref "U6") (pin "EN") (pinfunction "EN_EN") (pintype "bidirectional"))
    )
    (net (code "75") (name "Net-(U2-CREF)") (class "Default")
      (node (ref "R1") (pin "2") (pinfunction "2_2") (pintype "passive"))
      (node (ref "U2") (pin "23") (pinfunction "CREF_23") (pintype "bidirectional"))
    )
    (net (code "76") (name "Net-(U2-OUT3)") (class "Default")
      (node (ref "R19") (pin "1") (pinfunction "1_1") (pintype "passive"))
      (node (ref "U2") (pin "8") (pinfunction "OUT3_8") (pintype "bidirectional"))
    )
    (net (code "77") (name "Net-(U2-OUT7)") (class "Default")
      (node (ref "R20") (pin "1") (pinfunction "1_1") (pintype "passive"))
      (node (ref "U2") (pin "12") (pinfunction "OUT7_12") (pintype "bidirectional"))
    )
    (net (code "78") (name "Net-(U4-CREF)") (class "Default")
      (node (ref "R9") (pin "2") (pinfunction "2_2") (pintype "passive"))
      (node (ref "U4") (pin "23") (pinfunction "CREF_23") (pintype "bidirectional"))
    )
    (net (code "79") (name "Net-(U5-BP)") (class "Default")
      (node (ref "C16") (pin "1") (pinfunction "1_1") (pintype "passive"))
      (node (ref "U5") (pin "4") (pinfunction "BP_4") (pintype "input"))
    )
    (net (code "80") (name "RCOL0") (class "Default")
      (node (ref "LED_1") (pin "1") (pinfunction "RED_1") (pintype "bidirectional"))
      (node (ref "LED_17") (pin "1") (pinfunction "RED_1") (pintype "bidirectional"))
      (node (ref "LED_25") (pin "1") (pinfunction "RED_1") (pintype "bidirectional"))
      (node (ref "LED_33") (pin "1") (pinfunction "RED_1") (pintype "bidirectional"))
      (node (ref "LED_41") (pin "1") (pinfunction "RED_1") (pintype "bidirectional"))
      (node (ref "LED_49") (pin "1") (pinfunction "RED_1") (pintype "bidirectional"))
      (node (ref "LED_57") (pin "1") (pinfunction "RED_1") (pintype "bidirectional"))
      (node (ref "LED_9") (pin "1") (pinfunction "RED_1") (pintype "bidirectional"))
      (node (ref "R19") (pin "5") (pinfunction "2_5") (pintype "passive"))
    )
    (net (code "81") (name "RCOL1") (class "Default")
      (node (ref "LED_10") (pin "1") (pinfunction "RED_1") (pintype "bidirectional"))
      (node (ref "LED_18") (pin "1") (pinfunction "RED_1") (pintype "bidirectional"))
      (node (ref "LED_2") (pin "1") (pinfunction "RED_1") (pintype "bidirectional"))
      (node (ref "LED_26") (pin "1") (pinfunction "RED_1") (pintype "bidirectional"))
      (node (ref "LED_34") (pin "1") (pinfunction "RED_1") (pintype "bidirectional"))
      (node (ref "LED_42") (pin "1") (pinfunction "RED_1") (pintype "bidirectional"))
      (node (ref "LED_50") (pin "1") (pinfunction "RED_1") (pintype "bidirectional"))
      (node (ref "LED_58") (pin "1") (pinfunction "RED_1") (pintype "bidirectional"))
      (node (ref "R19") (pin "6") (pinfunction "2_6") (pintype "passive"))
    )
    (net (code "82") (name "RCOL2") (class "Default")
      (node (ref "LED_11") (pin "1") (pinfunction "RED_1") (pintype "bidirectional"))
      (node (ref "LED_19") (pin "1") (pinfunction "RED_1") (pintype "bidirectional"))
      (node (ref "LED_27") (pin "1") (pinfunction "RED_1") (pintype "bidirectional"))
      (node (ref "LED_3") (pin "1") (pinfunction "RED_1") (pintype "bidirectional"))
      (node (ref "LED_35") (pin "1") (pinfunction "RED_1") (pintype "bidirectional"))
      (node (ref "LED_43") (pin "1") (pinfunction "RED_1") (pintype "bidirectional"))
      (node (ref "LED_51") (pin "1") (pinfunction "RED_1") (pintype "bidirectional"))
      (node (ref "LED_59") (pin "1") (pinfunction "RED_1") (pintype "bidirectional"))
      (node (ref "R19") (pin "7") (pinfunction "2_7") (pintype "passive"))
    )
    (net (code "83") (name "RCOL3") (class "Default")
      (node (ref "LED_12") (pin "1") (pinfunction "RED_1") (pintype "bidirectional"))
      (node (ref "LED_20") (pin "1") (pinfunction "RED_1") (pintype "bidirectional"))
      (node (ref "LED_28") (pin "1") (pinfunction "RED_1") (pintype "bidirectional"))
      (node (ref "LED_36") (pin "1") (pinfunction "RED_1") (pintype "bidirectional"))
      (node (ref "LED_4") (pin "1") (pinfunction "RED_1") (pintype "bidirectional"))
      (node (ref "LED_44") (pin "1") (pinfunction "RED_1") (pintype "bidirectional"))
      (node (ref "LED_52") (pin "1") (pinfunction "RED_1") (pintype "bidirectional"))
      (node (ref "LED_60") (pin "1") (pinfunction "RED_1") (pintype "bidirectional"))
      (node (ref "R19") (pin "8") (pinfunction "2_8") (pintype "passive"))
    )
    (net (code "84") (name "RCOL4") (class "Default")
      (node (ref "LED_13") (pin "1") (pinfunction "RED_1") (pintype "bidirectional"))
      (node (ref "LED_21") (pin "1") (pinfunction "RED_1") (pintype "bidirectional"))
      (node (ref "LED_29") (pin "1") (pinfunction "RED_1") (pintype "bidirectional"))
      (node (ref "LED_37") (pin "1") (pinfunction "RED_1") (pintype "bidirectional"))
      (node (ref "LED_45") (pin "1") (pinfunction "RED_1") (pintype "bidirectional"))
      (node (ref "LED_5") (pin "1") (pinfunction "RED_1") (pintype "bidirectional"))
      (node (ref "LED_53") (pin "1") (pinfunction "RED_1") (pintype "bidirectional"))
      (node (ref "LED_61") (pin "1") (pinfunction "RED_1") (pintype "bidirectional"))
      (node (ref "R20") (pin "5") (pinfunction "2_5") (pintype "passive"))
    )
    (net (code "85") (name "RCOL5") (class "Default")
      (node (ref "LED_14") (pin "1") (pinfunction "RED_1") (pintype "bidirectional"))
      (node (ref "LED_22") (pin "1") (pinfunction "RED_1") (pintype "bidirectional"))
      (node (ref "LED_30") (pin "1") (pinfunction "RED_1") (pintype "bidirectional"))
      (node (ref "LED_38") (pin "1") (pinfunction "RED_1") (pintype "bidirectional"))
      (node (ref "LED_46") (pin "1") (pinfunction "RED_1") (pintype "bidirectional"))
      (node (ref "LED_54") (pin "1") (pinfunction "RED_1") (pintype "bidirectional"))
      (node (ref "LED_6") (pin "1") (pinfunction "RED_1") (pintype "bidirectional"))
      (node (ref "LED_62") (pin "1") (pinfunction "RED_1") (pintype "bidirectional"))
      (node (ref "R20") (pin "6") (pinfunction "2_6") (pintype "passive"))
    )
    (net (code "86") (name "RCOL6") (class "Default")
      (node (ref "LED_15") (pin "1") (pinfunction "RED_1") (pintype "bidirectional"))
      (node (ref "LED_23") (pin "1") (pinfunction "RED_1") (pintype "bidirectional"))
      (node (ref "LED_31") (pin "1") (pinfunction "RED_1") (pintype "bidirectional"))
      (node (ref "LED_39") (pin "1") (pinfunction "RED_1") (pintype "bidirectional"))
      (node (ref "LED_47") (pin "1") (pinfunction "RED_1") (pintype "bidirectional"))
      (node (ref "LED_55") (pin "1") (pinfunction "RED_1") (pintype "bidirectional"))
      (node (ref "LED_63") (pin "1") (pinfunction "RED_1") (pintype "bidirectional"))
      (node (ref "LED_7") (pin "1") (pinfunction "RED_1") (pintype "bidirectional"))
      (node (ref "R20") (pin "7") (pinfunction "2_7") (pintype "passive"))
    )
    (net (code "87") (name "RCOL7") (class "Default")
      (node (ref "LED_16") (pin "1") (pinfunction "RED_1") (pintype "bidirectional"))
      (node (ref "LED_24") (pin "1") (pinfunction "RED_1") (pintype "bidirectional"))
      (node (ref "LED_32") (pin "1") (pinfunction "RED_1") (pintype "bidirectional"))
      (node (ref "LED_40") (pin "1") (pinfunction "RED_1") (pintype "bidirectional"))
      (node (ref "LED_48") (pin "1") (pinfunction "RED_1") (pintype "bidirectional"))
      (node (ref "LED_56") (pin "1") (pinfunction "RED_1") (pintype "bidirectional"))
      (node (ref "LED_64") (pin "1") (pinfunction "RED_1") (pintype "bidirectional"))
      (node (ref "LED_8") (pin "1") (pinfunction "RED_1") (pintype "bidirectional"))
      (node (ref "R20") (pin "8") (pinfunction "2_8") (pintype "passive"))
    )
    (net (code "88") (name "USB_5V") (class "Default")
      (node (ref "C17") (pin "1") (pinfunction "1_1") (pintype "passive"))
      (node (ref "D3") (pin "A") (pinfunction "A_A") (pintype "passive"))
      (node (ref "J1") (pin "PIN$1") (pinfunction "VCC_PIN$1") (pintype "bidirectional"))
      (node (ref "U7") (pin "4") (pinfunction "VCC_4") (pintype "bidirectional"))
    )
    (net (code "89") (name "USB_D+") (class "Default")
      (node (ref "R8") (pin "2") (pinfunction "2_2") (pintype "passive"))
      (node (ref "U1") (pin "3") (pinfunction "USB0_DP_3") (pintype "bidirectional"))
    )
    (net (code "90") (name "USB_D-") (class "Default")
      (node (ref "R7") (pin "2") (pinfunction "2_2") (pintype "passive"))
      (node (ref "U1") (pin "4") (pinfunction "USB0_DM_4") (pintype "bidirectional"))
    )
    (net (code "91") (name "VBAT") (class "Default")
      (node (ref "C12") (pin "1") (pinfunction "1_1") (pintype "passive"))
      (node (ref "J3") (pin "+") (pinfunction "+_+") (pintype "bidirectional"))
      (node (ref "L1") (pin "P$1") (pinfunction "1_P$1") (pintype "passive"))
      (node (ref "U7") (pin "3") (pinfunction "BAT_3") (pintype "bidirectional"))
    )
    (net (code "92") (name "unconnected-(J1-ID-PadPIN$4)") (class "Default")
      (node (ref "J1") (pin "PIN$4") (pinfunction "ID_PIN$4") (pintype "bidirectional"))
    )
    (net (code "93") (name "unconnected-(U1-EXTAL32-Pad10)") (class "Default")
      (node (ref "U1") (pin "10") (pinfunction "EXTAL32_10") (pintype "bidirectional"))
    )
    (net (code "94") (name "unconnected-(U1-PTC2-Pad23)") (class "Default")
      (node (ref "U1") (pin "23") (pinfunction "PTC2_23") (pintype "bidirectional"))
    )
    (net (code "95") (name "unconnected-(U1-PTC7-Pad28)") (class "Default")
      (node (ref "U1") (pin "28") (pinfunction "PTC7_28") (pintype "bidirectional"))
    )
    (net (code "96") (name "unconnected-(U1-XTAL32-Pad9)") (class "Default")
      (node (ref "U1") (pin "9") (pinfunction "XTAL32_9") (pintype "bidirectional"))
    )
    (net (code "97") (name "unconnected-(U4-DOUT-Pad22)") (class "Default")
      (node (ref "U4") (pin "22") (pinfunction "DOUT_22") (pintype "bidirectional"))
    )
    (net (code "98") (name "unconnected-(U4-OUT8-Pad13)") (class "Default")
      (node (ref "U4") (pin "13") (pinfunction "OUT8_13") (pintype "bidirectional"))
    )
    (net (code "99") (name "unconnected-(U4-OUT9-Pad14)") (class "Default")
      (node (ref "U4") (pin "14") (pinfunction "OUT9_14") (pintype "bidirectional"))
    )
    (net (code "100") (name "unconnected-(U4-OUT10-Pad15)") (class "Default")
      (node (ref "U4") (pin "15") (pinfunction "OUT10_15") (pintype "bidirectional"))
    )
    (net (code "101") (name "unconnected-(U4-OUT11-Pad16)") (class "Default")
      (node (ref "U4") (pin "16") (pinfunction "OUT11_16") (pintype "bidirectional"))
    )
    (net (code "102") (name "unconnected-(U4-OUT12-Pad17)") (class "Default")
      (node (ref "U4") (pin "17") (pinfunction "OUT12_17") (pintype "bidirectional"))
    )
    (net (code "103") (name "unconnected-(U4-OUT13-Pad18)") (class "Default")
      (node (ref "U4") (pin "18") (pinfunction "OUT13_18") (pintype "bidirectional"))
    )
    (net (code "104") (name "unconnected-(U4-OUT14-Pad19)") (class "Default")
      (node (ref "U4") (pin "19") (pinfunction "OUT14_19") (pintype "bidirectional"))
    )
    (net (code "105") (name "unconnected-(U4-OUT15-Pad20)") (class "Default")
      (node (ref "U4") (pin "20") (pinfunction "OUT15_20") (pintype "bidirectional"))
    )
  )
)
